# remote_v0_9.net
KiCad netlist of a schematic drawn in EAGLE
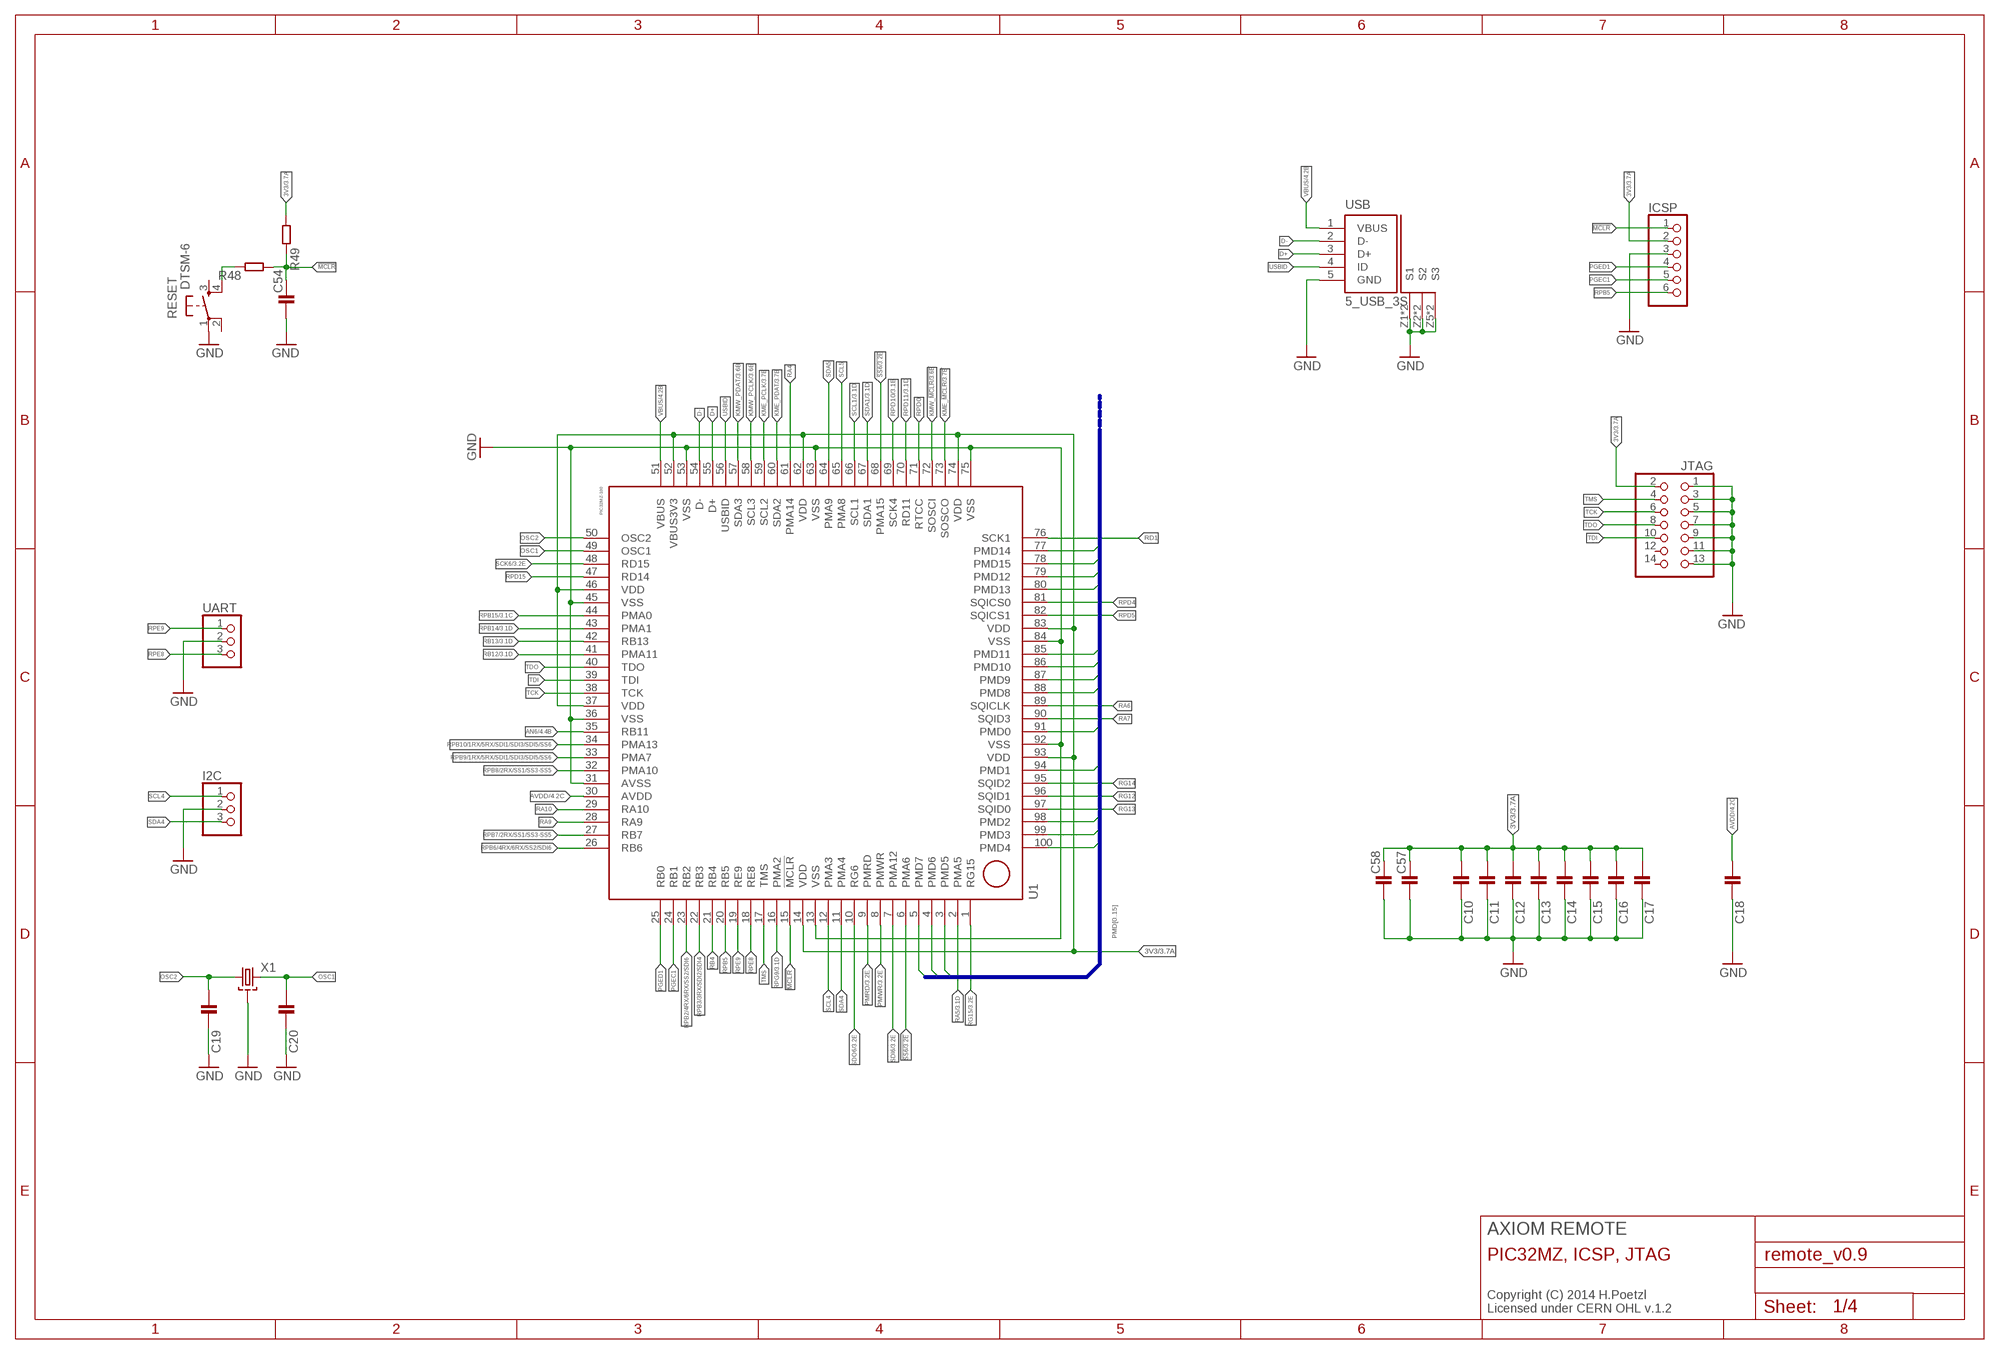
[diagram p0: schematic, sheet 1]
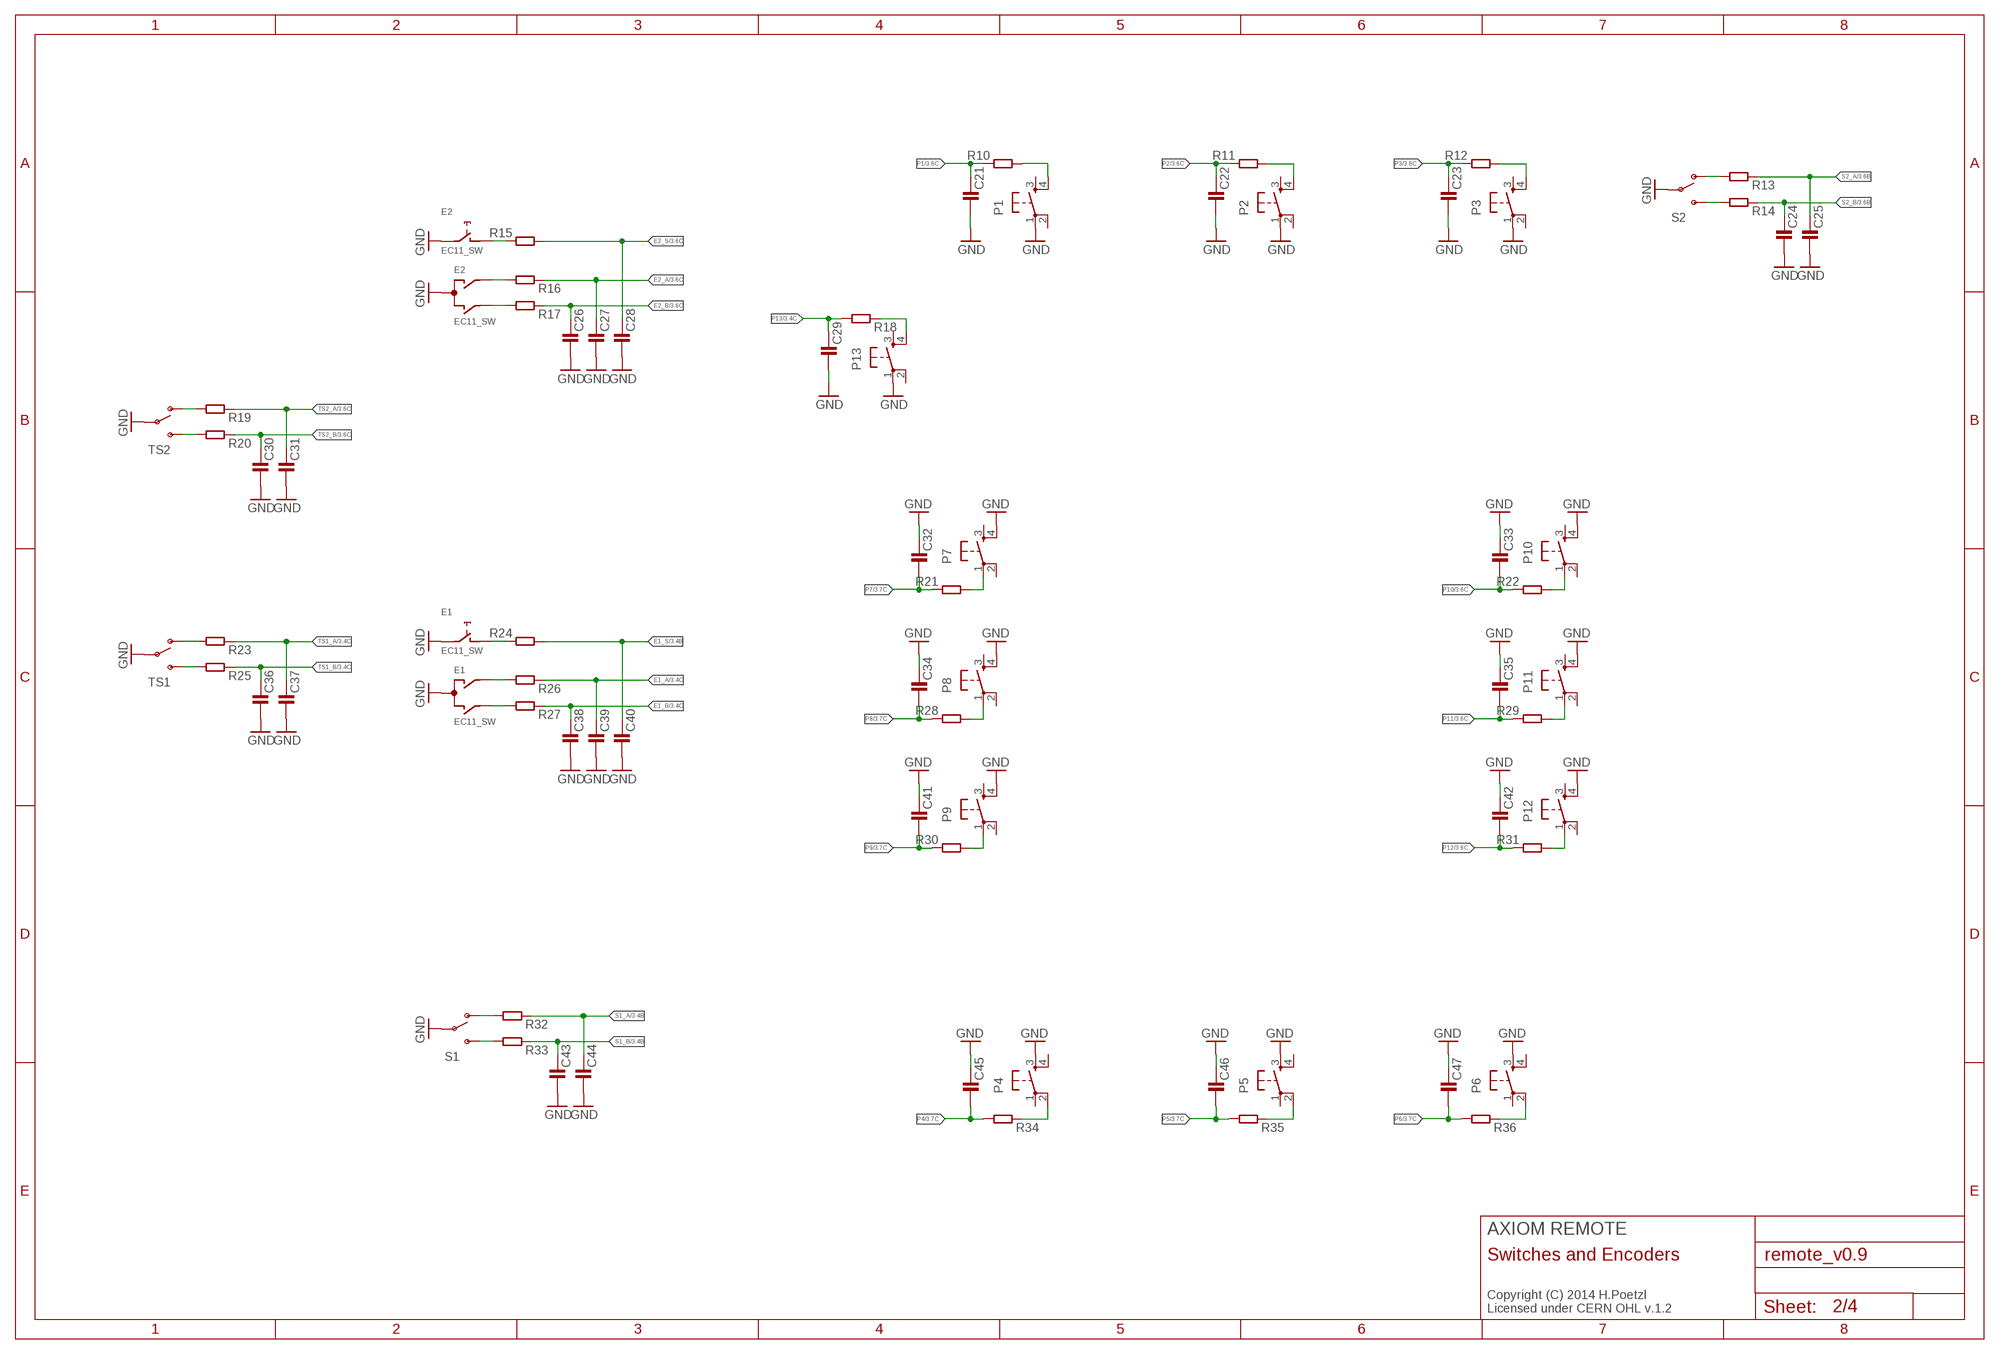
[diagram p1: schematic, sheet 2]
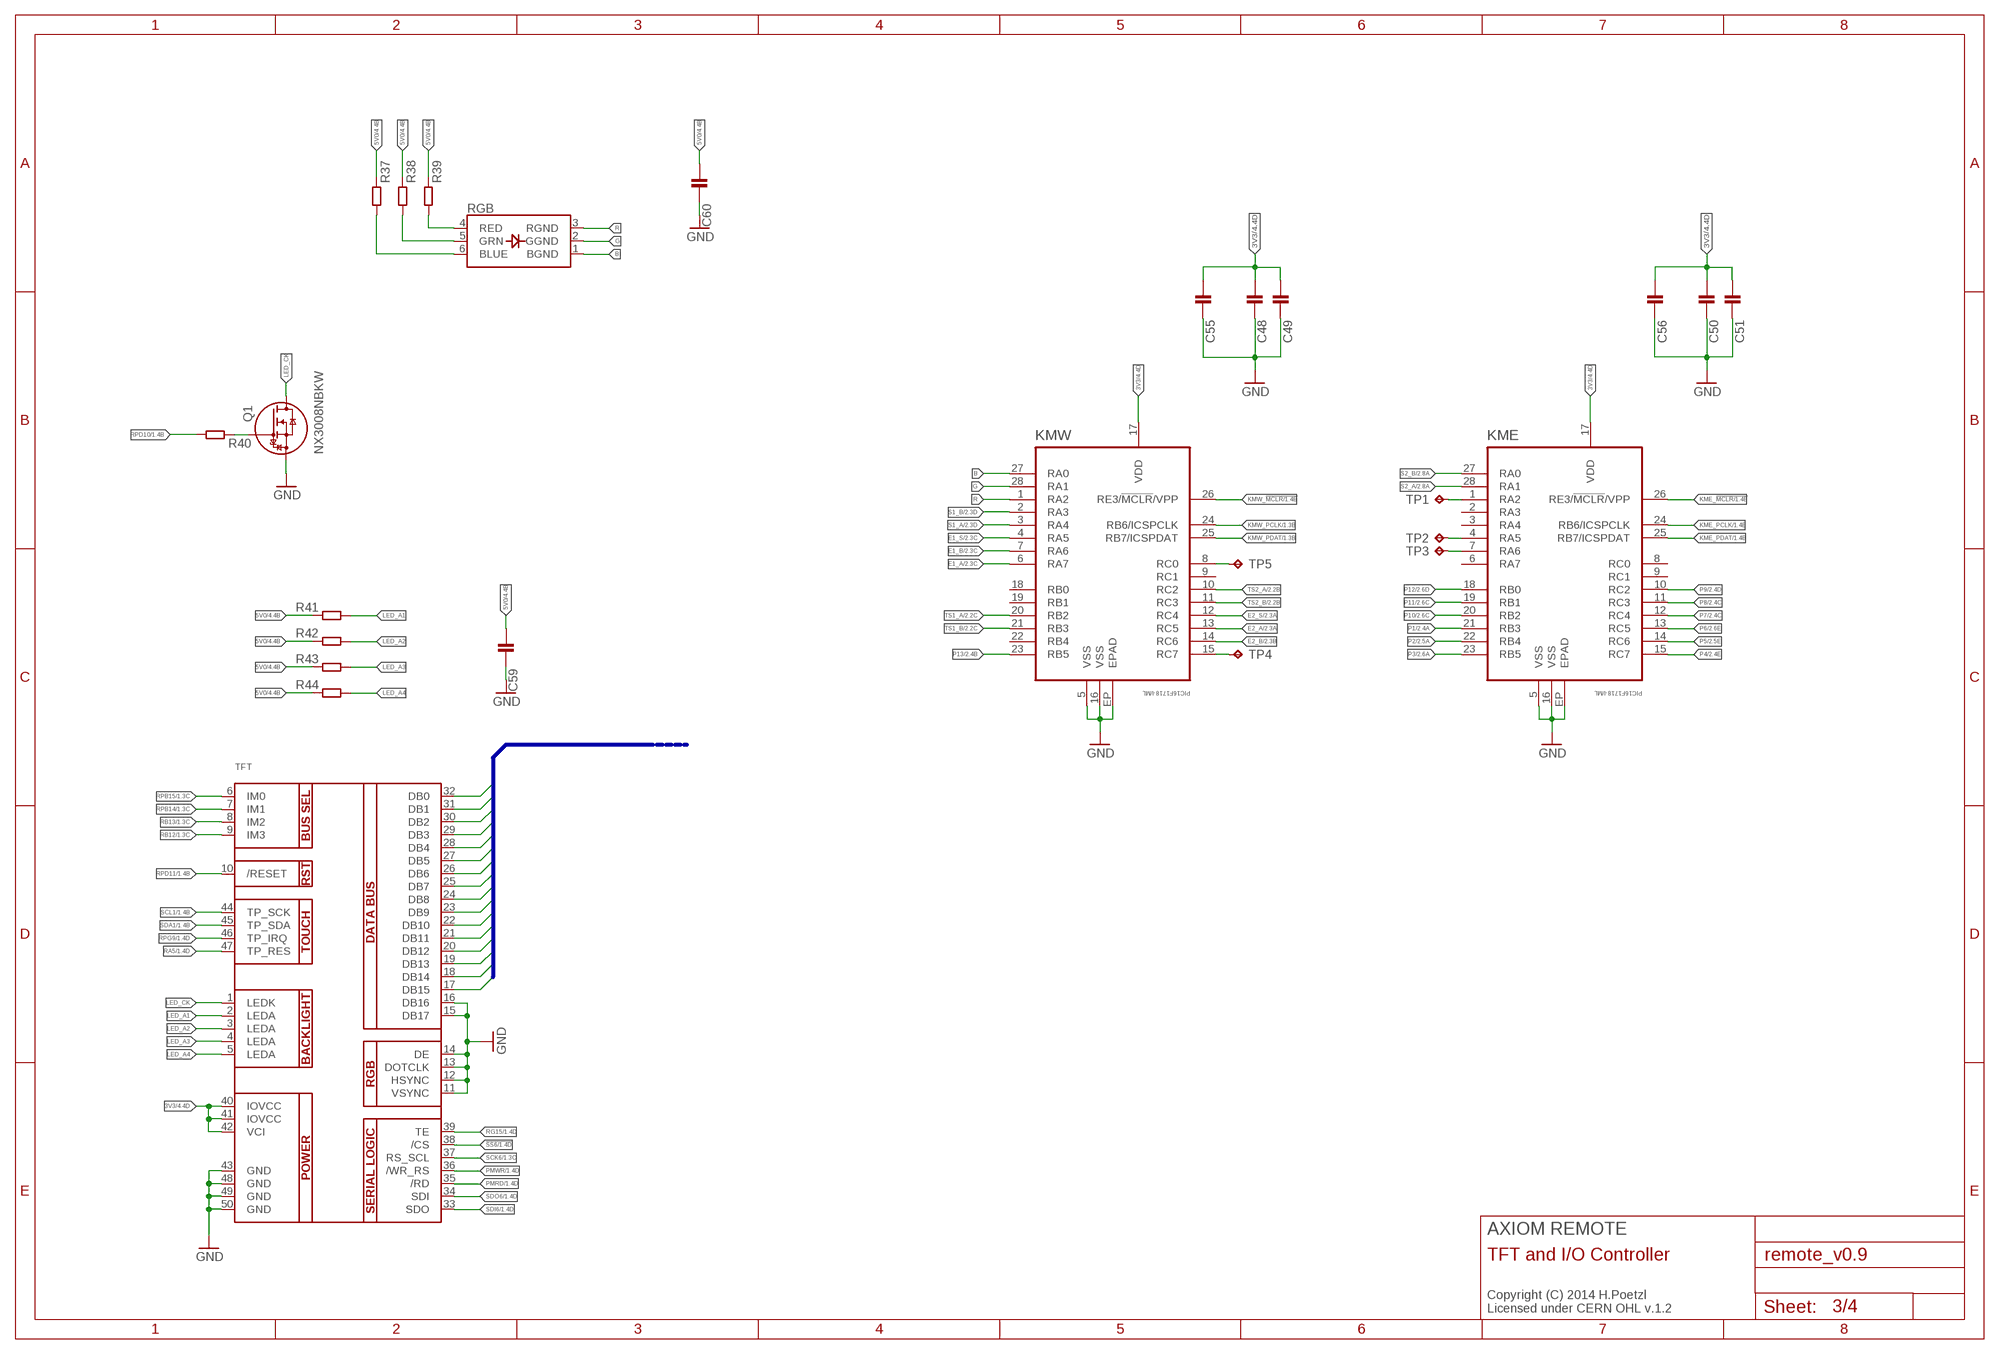
[diagram p2: schematic, sheet 3]
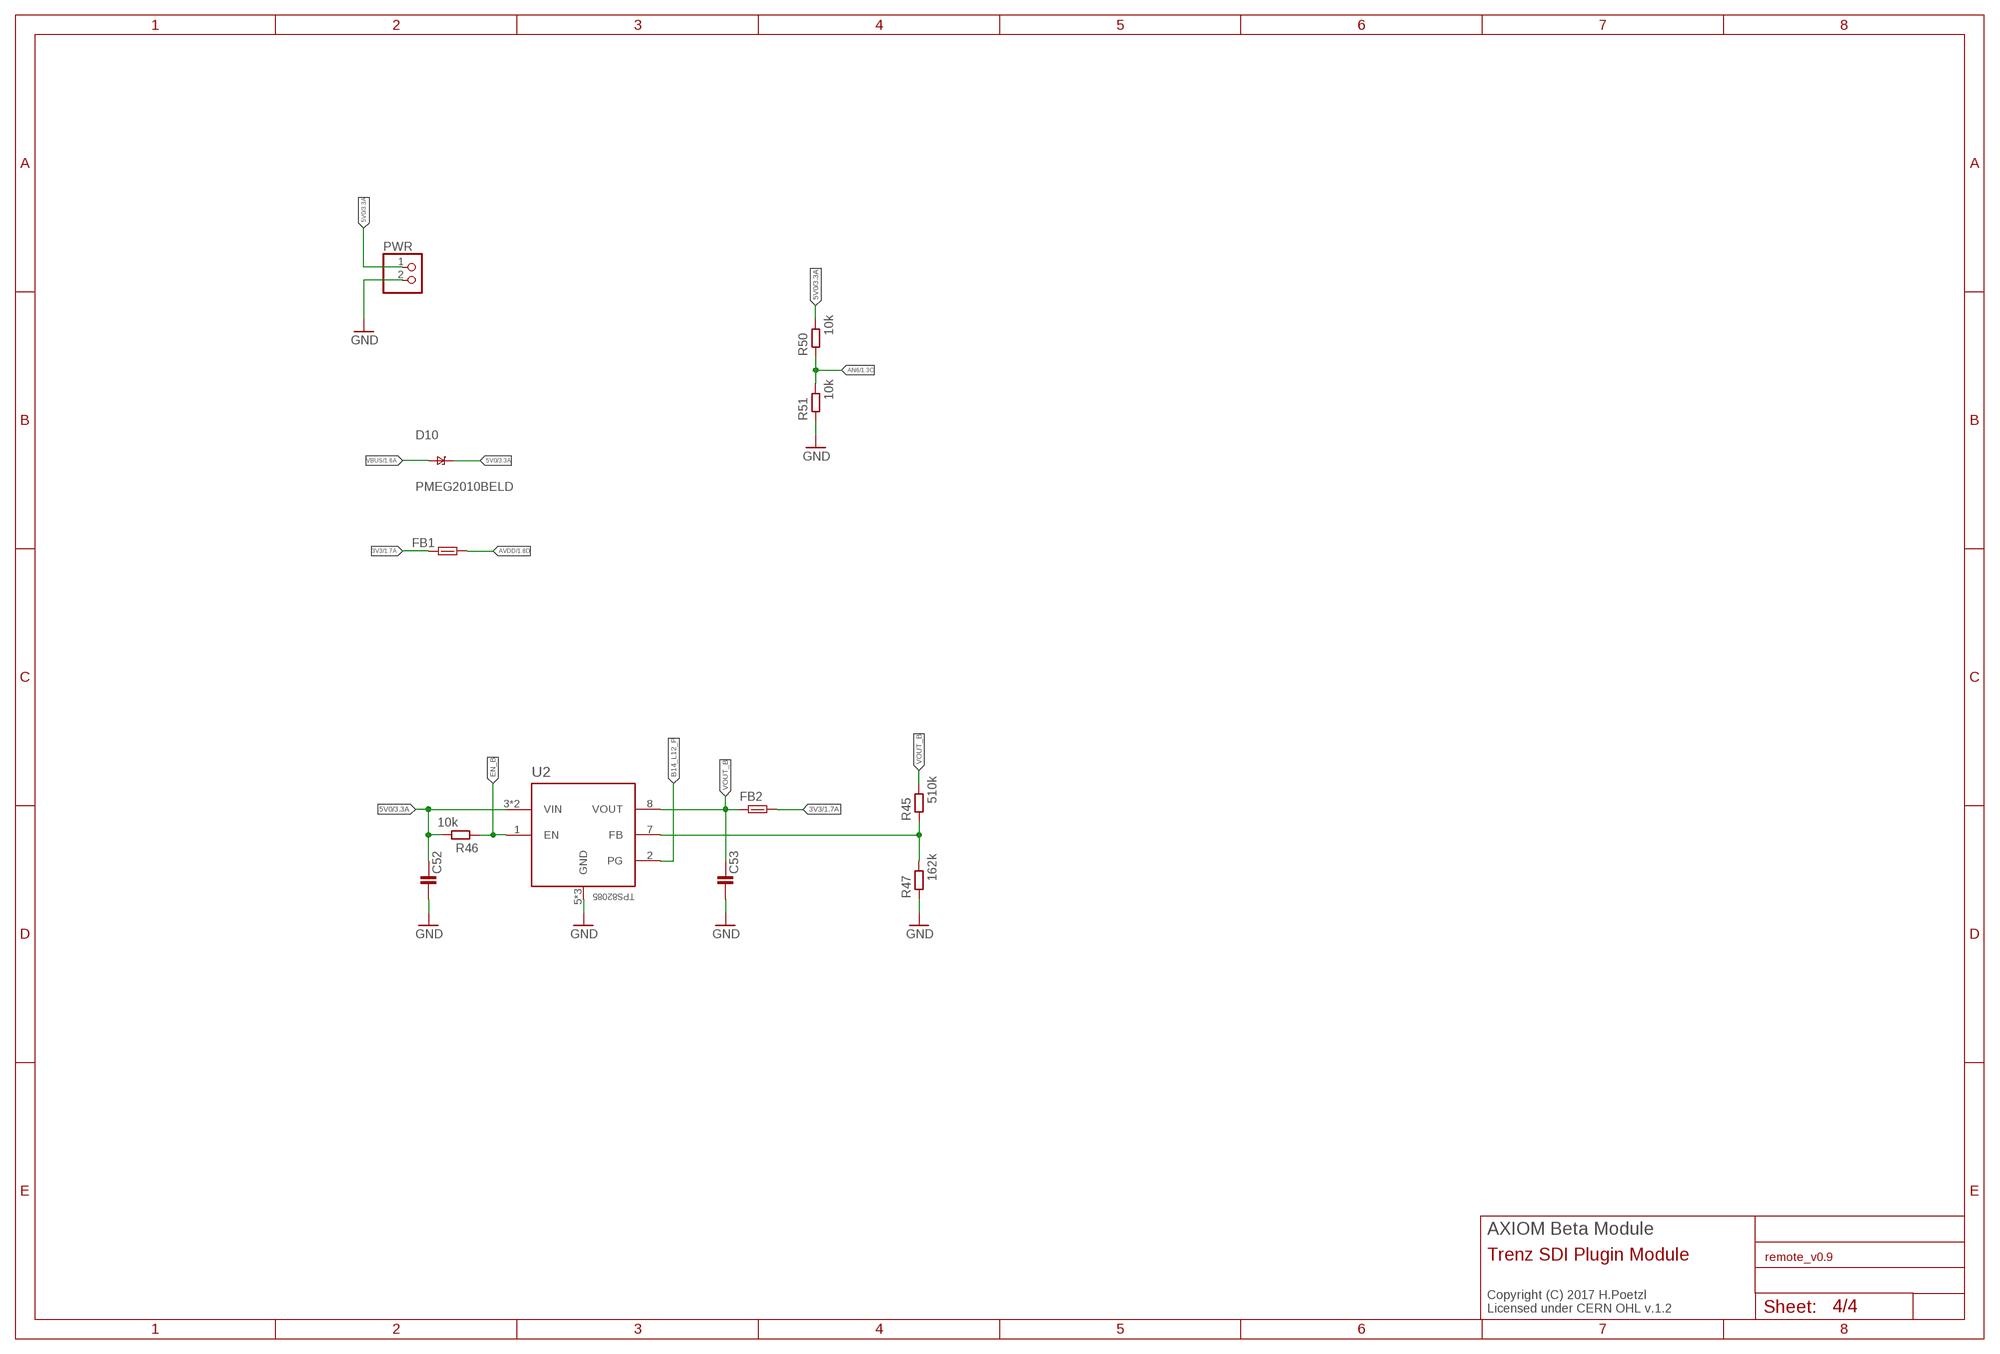
[diagram p3: schematic, sheet 4]

(export (version "E")
  (design (tool "Eeschema 10.0.6"))
  (components
    (comp (ref "C48")
      (value "100n")
      (footprint "eagle-import:0402-C")
      (libsource (lib "eagle-import") (part "C0402-C"))
    )
    (comp (ref "C49")
      (value "100n")
      (footprint "eagle-import:0402-C")
      (libsource (lib "eagle-import") (part "C0402-C"))
    )
    (comp (ref "C50")
      (value "100n")
      (footprint "eagle-import:0402-C")
      (libsource (lib "eagle-import") (part "C0402-C"))
    )
    (comp (ref "C51")
      (value "100n")
      (footprint "eagle-import:0402-C")
      (libsource (lib "eagle-import") (part "C0402-C"))
    )
    (comp (ref "C55")
      (value "100n")
      (footprint "eagle-import:0805-C")
      (libsource (lib "eagle-import") (part "C0805-C"))
    )
    (comp (ref "C56")
      (value "100n")
      (footprint "eagle-import:0805-C")
      (libsource (lib "eagle-import") (part "C0805-C"))
    )
    (comp (ref "C59")
      (value "100n")
      (footprint "eagle-import:0805-C")
      (libsource (lib "eagle-import") (part "C0805-C"))
    )
    (comp (ref "C60")
      (value "100n")
      (footprint "eagle-import:0805-C")
      (libsource (lib "eagle-import") (part "C0805-C"))
    )
    (comp (ref "KME")
      (value "PIC16F1718-I/ML")
      (footprint "eagle-import:QFN65P600X600X100-29N")
      (libsource (lib "eagle-import") (part "PIC16F1718-I/ML"))
    )
    (comp (ref "KMW")
      (value "PIC16F1718-I/ML")
      (footprint "eagle-import:QFN65P600X600X100-29N")
      (libsource (lib "eagle-import") (part "PIC16F1718-I/ML"))
    )
    (comp (ref "Q1")
      (value "NX3008NBKW")
      (footprint "eagle-import:SOT323")
      (libsource (lib "eagle-import") (part "NX3008NBKW"))
    )
    (comp (ref "R37")
      (value "R0603-C")
      (footprint "eagle-import:0603-C")
      (libsource (lib "eagle-import") (part "R0603-C"))
    )
    (comp (ref "R38")
      (value "R0603-C")
      (footprint "eagle-import:0603-C")
      (libsource (lib "eagle-import") (part "R0603-C"))
    )
    (comp (ref "R39")
      (value "R0603-C")
      (footprint "eagle-import:0603-C")
      (libsource (lib "eagle-import") (part "R0603-C"))
    )
    (comp (ref "R40")
      (value "R0402-C")
      (footprint "eagle-import:0402-C")
      (libsource (lib "eagle-import") (part "R0402-C"))
    )
    (comp (ref "R41")
      (value "R0805-C")
      (footprint "eagle-import:0805-C")
      (libsource (lib "eagle-import") (part "R0805-C"))
    )
    (comp (ref "R42")
      (value "R0805-C")
      (footprint "eagle-import:0805-C")
      (libsource (lib "eagle-import") (part "R0805-C"))
    )
    (comp (ref "R43")
      (value "R0805-C")
      (footprint "eagle-import:0805-C")
      (libsource (lib "eagle-import") (part "R0805-C"))
    )
    (comp (ref "R44")
      (value "R0805-C")
      (footprint "eagle-import:0805-C")
      (libsource (lib "eagle-import") (part "R0805-C"))
    )
    (comp (ref "RGB")
      (value "LED_RGB_PLCC6CREE-CLV6A")
      (footprint "eagle-import:RGBLED_PLCC6")
      (libsource (lib "eagle-import") (part "LED_RGB_PLCC6CREE-CLV6A"))
    )
    (comp (ref "TFT")
      (value "DISP_LCD_CTP28_SAMPLE")
      (footprint "eagle-import:TFT_2.83IN_240X320_50PIN")
      (libsource (lib "eagle-import") (part "DISP_LCD_CTP28_SAMPLE"))
    )
    (comp (ref "TP1")
      (value "TPTP12R")
      (footprint "eagle-import:TP12R")
      (libsource (lib "eagle-import") (part "TPTP12R"))
    )
    (comp (ref "TP2")
      (value "TPTP12R")
      (footprint "eagle-import:TP12R")
      (libsource (lib "eagle-import") (part "TPTP12R"))
    )
    (comp (ref "TP3")
      (value "TPTP12R")
      (footprint "eagle-import:TP12R")
      (libsource (lib "eagle-import") (part "TPTP12R"))
    )
    (comp (ref "TP4")
      (value "TPTP12R")
      (footprint "eagle-import:TP12R")
      (libsource (lib "eagle-import") (part "TPTP12R"))
    )
    (comp (ref "TP5")
      (value "TPTP12R")
      (footprint "eagle-import:TP12R")
      (libsource (lib "eagle-import") (part "TPTP12R"))
    )
    (comp (ref "C52")
      (value "C0603-C")
      (footprint "eagle-import:0603-C")
      (libsource (lib "eagle-import") (part "C0603-C"))
    )
    (comp (ref "C53")
      (value "C0603-C")
      (footprint "eagle-import:0603-C")
      (libsource (lib "eagle-import") (part "C0603-C"))
    )
    (comp (ref "D10")
      (value "PMEG2010BELD")
      (footprint "eagle-import:DFN1006D-2")
      (libsource (lib "eagle-import") (part "PMEG2010BELD"))
    )
    (comp (ref "FB1")
      (value "FB0402-C")
      (footprint "eagle-import:0402-C")
      (libsource (lib "eagle-import") (part "FB0402-C"))
    )
    (comp (ref "FB2")
      (value "FB0603-C")
      (footprint "eagle-import:0603-C")
      (libsource (lib "eagle-import") (part "FB0603-C"))
    )
    (comp (ref "PWR")
      (value "PINHD-1X02_2.54-90°")
      (footprint "eagle-import:1X02_90")
      (libsource (lib "eagle-import") (part "PINHD-1X02_2.54-90°"))
    )
    (comp (ref "R45")
      (value "510k")
      (footprint "eagle-import:0201-C")
      (libsource (lib "eagle-import") (part "R0201-C"))
    )
    (comp (ref "R46")
      (value "10k")
      (footprint "eagle-import:0201-C")
      (libsource (lib "eagle-import") (part "R0201-C"))
    )
    (comp (ref "R47")
      (value "162k")
      (footprint "eagle-import:0201-C")
      (libsource (lib "eagle-import") (part "R0201-C"))
    )
    (comp (ref "R50")
      (value "10k")
      (footprint "eagle-import:0402-C")
      (libsource (lib "eagle-import") (part "R0402-C"))
    )
    (comp (ref "R51")
      (value "10k")
      (footprint "eagle-import:0402-C")
      (libsource (lib "eagle-import") (part "R0402-C"))
    )
    (comp (ref "U2")
      (value "TPS82085")
      (footprint "eagle-import:MICROSIP")
      (libsource (lib "eagle-import") (part "TPS82085"))
    )
    (comp (ref "C21")
      (value "C0402-C")
      (footprint "eagle-import:0402-C")
      (libsource (lib "eagle-import") (part "C0402-C"))
    )
    (comp (ref "C22")
      (value "C0402-C")
      (footprint "eagle-import:0402-C")
      (libsource (lib "eagle-import") (part "C0402-C"))
    )
    (comp (ref "C23")
      (value "C0402-C")
      (footprint "eagle-import:0402-C")
      (libsource (lib "eagle-import") (part "C0402-C"))
    )
    (comp (ref "C24")
      (value "C0402-C")
      (footprint "eagle-import:0402-C")
      (libsource (lib "eagle-import") (part "C0402-C"))
    )
    (comp (ref "C25")
      (value "C0402-C")
      (footprint "eagle-import:0402-C")
      (libsource (lib "eagle-import") (part "C0402-C"))
    )
    (comp (ref "C26")
      (value "C0402-C")
      (footprint "eagle-import:0402-C")
      (libsource (lib "eagle-import") (part "C0402-C"))
    )
    (comp (ref "C27")
      (value "C0402-C")
      (footprint "eagle-import:0402-C")
      (libsource (lib "eagle-import") (part "C0402-C"))
    )
    (comp (ref "C28")
      (value "C0402-C")
      (footprint "eagle-import:0402-C")
      (libsource (lib "eagle-import") (part "C0402-C"))
    )
    (comp (ref "C29")
      (value "C0402-C")
      (footprint "eagle-import:0402-C")
      (libsource (lib "eagle-import") (part "C0402-C"))
    )
    (comp (ref "C30")
      (value "C0402-C")
      (footprint "eagle-import:0402-C")
      (libsource (lib "eagle-import") (part "C0402-C"))
    )
    (comp (ref "C31")
      (value "C0402-C")
      (footprint "eagle-import:0402-C")
      (libsource (lib "eagle-import") (part "C0402-C"))
    )
    (comp (ref "C32")
      (value "C0402-C")
      (footprint "eagle-import:0402-C")
      (libsource (lib "eagle-import") (part "C0402-C"))
    )
    (comp (ref "C33")
      (value "C0402-C")
      (footprint "eagle-import:0402-C")
      (libsource (lib "eagle-import") (part "C0402-C"))
    )
    (comp (ref "C34")
      (value "C0402-C")
      (footprint "eagle-import:0402-C")
      (libsource (lib "eagle-import") (part "C0402-C"))
    )
    (comp (ref "C35")
      (value "C0402-C")
      (footprint "eagle-import:0402-C")
      (libsource (lib "eagle-import") (part "C0402-C"))
    )
    (comp (ref "C36")
      (value "C0402-C")
      (footprint "eagle-import:0402-C")
      (libsource (lib "eagle-import") (part "C0402-C"))
    )
    (comp (ref "C37")
      (value "C0402-C")
      (footprint "eagle-import:0402-C")
      (libsource (lib "eagle-import") (part "C0402-C"))
    )
    (comp (ref "C38")
      (value "C0402-C")
      (footprint "eagle-import:0402-C")
      (libsource (lib "eagle-import") (part "C0402-C"))
    )
    (comp (ref "C39")
      (value "C0402-C")
      (footprint "eagle-import:0402-C")
      (libsource (lib "eagle-import") (part "C0402-C"))
    )
    (comp (ref "C40")
      (value "C0402-C")
      (footprint "eagle-import:0402-C")
      (libsource (lib "eagle-import") (part "C0402-C"))
    )
    (comp (ref "C41")
      (value "C0402-C")
      (footprint "eagle-import:0402-C")
      (libsource (lib "eagle-import") (part "C0402-C"))
    )
    (comp (ref "C42")
      (value "C0402-C")
      (footprint "eagle-import:0402-C")
      (libsource (lib "eagle-import") (part "C0402-C"))
    )
    (comp (ref "C43")
      (value "C0402-C")
      (footprint "eagle-import:0402-C")
      (libsource (lib "eagle-import") (part "C0402-C"))
    )
    (comp (ref "C44")
      (value "C0402-C")
      (footprint "eagle-import:0402-C")
      (libsource (lib "eagle-import") (part "C0402-C"))
    )
    (comp (ref "C45")
      (value "C0402-C")
      (footprint "eagle-import:0402-C")
      (libsource (lib "eagle-import") (part "C0402-C"))
    )
    (comp (ref "C46")
      (value "C0402-C")
      (footprint "eagle-import:0402-C")
      (libsource (lib "eagle-import") (part "C0402-C"))
    )
    (comp (ref "C47")
      (value "C0402-C")
      (footprint "eagle-import:0402-C")
      (libsource (lib "eagle-import") (part "C0402-C"))
    )
    (comp (ref "E1")
      (value "EC11_SW")
      (footprint "eagle-import:EC11_SW")
      (libsource (lib "eagle-import") (part "EC11_SW"))
    )
    (comp (ref "E2")
      (value "EC11_SW")
      (footprint "eagle-import:EC11_SW")
      (libsource (lib "eagle-import") (part "EC11_SW"))
    )
    (comp (ref "P1")
      (value "DTSM-6THT")
      (footprint "eagle-import:6X6-THT")
      (libsource (lib "eagle-import") (part "DTSM-6THT"))
    )
    (comp (ref "P2")
      (value "DTSM-6THT")
      (footprint "eagle-import:6X6-THT")
      (libsource (lib "eagle-import") (part "DTSM-6THT"))
    )
    (comp (ref "P3")
      (value "DTSM-6THT")
      (footprint "eagle-import:6X6-THT")
      (libsource (lib "eagle-import") (part "DTSM-6THT"))
    )
    (comp (ref "P4")
      (value "DTSM-6THT")
      (footprint "eagle-import:6X6-THT")
      (libsource (lib "eagle-import") (part "DTSM-6THT"))
    )
    (comp (ref "P5")
      (value "DTSM-6THT")
      (footprint "eagle-import:6X6-THT")
      (libsource (lib "eagle-import") (part "DTSM-6THT"))
    )
    (comp (ref "P6")
      (value "DTSM-6THT")
      (footprint "eagle-import:6X6-THT")
      (libsource (lib "eagle-import") (part "DTSM-6THT"))
    )
    (comp (ref "P7")
      (value "DTSM-6THT")
      (footprint "eagle-import:6X6-THT")
      (libsource (lib "eagle-import") (part "DTSM-6THT"))
    )
    (comp (ref "P8")
      (value "DTSM-6THT")
      (footprint "eagle-import:6X6-THT")
      (libsource (lib "eagle-import") (part "DTSM-6THT"))
    )
    (comp (ref "P9")
      (value "DTSM-6THT")
      (footprint "eagle-import:6X6-THT")
      (libsource (lib "eagle-import") (part "DTSM-6THT"))
    )
    (comp (ref "P10")
      (value "DTSM-6THT")
      (footprint "eagle-import:6X6-THT")
      (libsource (lib "eagle-import") (part "DTSM-6THT"))
    )
    (comp (ref "P11")
      (value "DTSM-6THT")
      (footprint "eagle-import:6X6-THT")
      (libsource (lib "eagle-import") (part "DTSM-6THT"))
    )
    (comp (ref "P12")
      (value "DTSM-6THT")
      (footprint "eagle-import:6X6-THT")
      (libsource (lib "eagle-import") (part "DTSM-6THT"))
    )
    (comp (ref "P13")
      (value "DTSM-6THT")
      (footprint "eagle-import:6X6-THT")
      (libsource (lib "eagle-import") (part "DTSM-6THT"))
    )
    (comp (ref "R10")
      (value "R0402-C")
      (footprint "eagle-import:0402-C")
      (libsource (lib "eagle-import") (part "R0402-C"))
    )
    (comp (ref "R11")
      (value "R0402-C")
      (footprint "eagle-import:0402-C")
      (libsource (lib "eagle-import") (part "R0402-C"))
    )
    (comp (ref "R12")
      (value "R0402-C")
      (footprint "eagle-import:0402-C")
      (libsource (lib "eagle-import") (part "R0402-C"))
    )
    (comp (ref "R13")
      (value "R0402-C")
      (footprint "eagle-import:0402-C")
      (libsource (lib "eagle-import") (part "R0402-C"))
    )
    (comp (ref "R14")
      (value "R0402-C")
      (footprint "eagle-import:0402-C")
      (libsource (lib "eagle-import") (part "R0402-C"))
    )
    (comp (ref "R15")
      (value "R0402-C")
      (footprint "eagle-import:0402-C")
      (libsource (lib "eagle-import") (part "R0402-C"))
    )
    (comp (ref "R16")
      (value "R0402-C")
      (footprint "eagle-import:0402-C")
      (libsource (lib "eagle-import") (part "R0402-C"))
    )
    (comp (ref "R17")
      (value "R0402-C")
      (footprint "eagle-import:0402-C")
      (libsource (lib "eagle-import") (part "R0402-C"))
    )
    (comp (ref "R18")
      (value "R0402-C")
      (footprint "eagle-import:0402-C")
      (libsource (lib "eagle-import") (part "R0402-C"))
    )
    (comp (ref "R19")
      (value "R0402-C")
      (footprint "eagle-import:0402-C")
      (libsource (lib "eagle-import") (part "R0402-C"))
    )
    (comp (ref "R20")
      (value "R0402-C")
      (footprint "eagle-import:0402-C")
      (libsource (lib "eagle-import") (part "R0402-C"))
    )
    (comp (ref "R21")
      (value "R0402-C")
      (footprint "eagle-import:0402-C")
      (libsource (lib "eagle-import") (part "R0402-C"))
    )
    (comp (ref "R22")
      (value "R0402-C")
      (footprint "eagle-import:0402-C")
      (libsource (lib "eagle-import") (part "R0402-C"))
    )
    (comp (ref "R23")
      (value "R0402-C")
      (footprint "eagle-import:0402-C")
      (libsource (lib "eagle-import") (part "R0402-C"))
    )
    (comp (ref "R24")
      (value "R0402-C")
      (footprint "eagle-import:0402-C")
      (libsource (lib "eagle-import") (part "R0402-C"))
    )
    (comp (ref "R25")
      (value "R0402-C")
      (footprint "eagle-import:0402-C")
      (libsource (lib "eagle-import") (part "R0402-C"))
    )
    (comp (ref "R26")
      (value "R0402-C")
      (footprint "eagle-import:0402-C")
      (libsource (lib "eagle-import") (part "R0402-C"))
    )
    (comp (ref "R27")
      (value "R0402-C")
      (footprint "eagle-import:0402-C")
      (libsource (lib "eagle-import") (part "R0402-C"))
    )
    (comp (ref "R28")
      (value "R0402-C")
      (footprint "eagle-import:0402-C")
      (libsource (lib "eagle-import") (part "R0402-C"))
    )
    (comp (ref "R29")
      (value "R0402-C")
      (footprint "eagle-import:0402-C")
      (libsource (lib "eagle-import") (part "R0402-C"))
    )
    (comp (ref "R30")
      (value "R0402-C")
      (footprint "eagle-import:0402-C")
      (libsource (lib "eagle-import") (part "R0402-C"))
    )
    (comp (ref "R31")
      (value "R0402-C")
      (footprint "eagle-import:0402-C")
      (libsource (lib "eagle-import") (part "R0402-C"))
    )
    (comp (ref "R32")
      (value "R0402-C")
      (footprint "eagle-import:0402-C")
      (libsource (lib "eagle-import") (part "R0402-C"))
    )
    (comp (ref "R33")
      (value "R0402-C")
      (footprint "eagle-import:0402-C")
      (libsource (lib "eagle-import") (part "R0402-C"))
    )
    (comp (ref "R34")
      (value "R0402-C")
      (footprint "eagle-import:0402-C")
      (libsource (lib "eagle-import") (part "R0402-C"))
    )
    (comp (ref "R35")
      (value "R0402-C")
      (footprint "eagle-import:0402-C")
      (libsource (lib "eagle-import") (part "R0402-C"))
    )
    (comp (ref "R36")
      (value "R0402-C")
      (footprint "eagle-import:0402-C")
      (libsource (lib "eagle-import") (part "R0402-C"))
    )
    (comp (ref "S1")
      (value "SWITCH-SPDTTHT")
      (footprint "eagle-import:1101M2S3CBE2")
      (libsource (lib "eagle-import") (part "SWITCH-SPDTTHT"))
    )
    (comp (ref "S2")
      (value "SWITCH-SPDTTHT-RA")
      (footprint "eagle-import:1101M2S3ABE2")
      (libsource (lib "eagle-import") (part "SWITCH-SPDTTHT-RA"))
    )
    (comp (ref "TS1")
      (value "SWITCH-SPDTSTG-RA")
      (footprint "eagle-import:200SPXTXBXM6")
      (libsource (lib "eagle-import") (part "SWITCH-SPDTSTG-RA"))
    )
    (comp (ref "TS2")
      (value "SWITCH-SPDTSTG-RA")
      (footprint "eagle-import:200SPXTXBXM6")
      (libsource (lib "eagle-import") (part "SWITCH-SPDTSTG-RA"))
    )
    (comp (ref "C10")
      (value "100n")
      (footprint "eagle-import:0402-C")
      (libsource (lib "eagle-import") (part "C0402-C"))
    )
    (comp (ref "C11")
      (value "100n")
      (footprint "eagle-import:0402-C")
      (libsource (lib "eagle-import") (part "C0402-C"))
    )
    (comp (ref "C12")
      (value "100n")
      (footprint "eagle-import:0402-C")
      (libsource (lib "eagle-import") (part "C0402-C"))
    )
    (comp (ref "C13")
      (value "100n")
      (footprint "eagle-import:0402-C")
      (libsource (lib "eagle-import") (part "C0402-C"))
    )
    (comp (ref "C14")
      (value "100n")
      (footprint "eagle-import:0402-C")
      (libsource (lib "eagle-import") (part "C0402-C"))
    )
    (comp (ref "C15")
      (value "100n")
      (footprint "eagle-import:0402-C")
      (libsource (lib "eagle-import") (part "C0402-C"))
    )
    (comp (ref "C16")
      (value "100n")
      (footprint "eagle-import:0402-C")
      (libsource (lib "eagle-import") (part "C0402-C"))
    )
    (comp (ref "C17")
      (value "100n")
      (footprint "eagle-import:0402-C")
      (libsource (lib "eagle-import") (part "C0402-C"))
    )
    (comp (ref "C18")
      (value "100n")
      (footprint "eagle-import:0402-C")
      (libsource (lib "eagle-import") (part "C0402-C"))
    )
    (comp (ref "C19")
      (value "100n")
      (footprint "eagle-import:0402-C")
      (libsource (lib "eagle-import") (part "C0402-C"))
    )
    (comp (ref "C20")
      (value "100n")
      (footprint "eagle-import:0402-C")
      (libsource (lib "eagle-import") (part "C0402-C"))
    )
    (comp (ref "C54")
      (value "C0402-C")
      (footprint "eagle-import:0402-C")
      (libsource (lib "eagle-import") (part "C0402-C"))
    )
    (comp (ref "C57")
      (value "C0805-C")
      (footprint "eagle-import:0805-C")
      (libsource (lib "eagle-import") (part "C0805-C"))
    )
    (comp (ref "C58")
      (value "C0805-C")
      (footprint "eagle-import:0805-C")
      (libsource (lib "eagle-import") (part "C0805-C"))
    )
    (comp (ref "I2C")
      (value "PINHD-1X03_2.54-90°")
      (footprint "eagle-import:1X03_90")
      (libsource (lib "eagle-import") (part "PINHD-1X03_2.54-90°"))
    )
    (comp (ref "ICSP")
      (value "PINHD-1X6/90")
      (footprint "eagle-import:1X06_90")
      (libsource (lib "eagle-import") (part "PINHD-1X6/90"))
    )
    (comp (ref "JTAG")
      (value "PINHD-2X07_2.00")
      (footprint "eagle-import:2X07M")
      (libsource (lib "eagle-import") (part "PINHD-2X07_2.00"))
    )
    (comp (ref "R48")
      (value "R0402-C")
      (footprint "eagle-import:0402-C")
      (libsource (lib "eagle-import") (part "R0402-C"))
    )
    (comp (ref "R49")
      (value "R0402-C")
      (footprint "eagle-import:0402-C")
      (libsource (lib "eagle-import") (part "R0402-C"))
    )
    (comp (ref "RESET")
      (value "DTSM-6")
      (footprint "eagle-import:3X4MM")
      (libsource (lib "eagle-import") (part "DTSM-6"))
    )
    (comp (ref "U1")
      (value "PIC32MZ-100")
      (footprint "eagle-import:QFP40P1400X1400X120-100N")
      (libsource (lib "eagle-import") (part "PIC32MZ-100"))
    )
    (comp (ref "UART")
      (value "PINHD-1X03_2.54-90°")
      (footprint "eagle-import:1X03_90")
      (libsource (lib "eagle-import") (part "PINHD-1X03_2.54-90°"))
    )
    (comp (ref "USB")
      (value "5_USB_3S")
      (footprint "eagle-import:MICRO-AB-H-SMT")
      (libsource (lib "eagle-import") (part "5_USB_3S"))
    )
    (comp (ref "X1")
      (value "SMD-4P-2G-2.0X1.6")
      (footprint "eagle-import:2.0X1.6")
      (libsource (lib "eagle-import") (part "SMD-4P-2G-2.0X1.6"))
    )
  )
  (nets
    (net (code "2") (name "3V3") (class "Default")
      (node (ref "C10") (pin "1") (pinfunction "1_1") (pintype "passive"))
      (node (ref "C11") (pin "1") (pinfunction "1_1") (pintype "passive"))
      (node (ref "C12") (pin "1") (pinfunction "1_1") (pintype "passive"))
      (node (ref "C13") (pin "1") (pinfunction "1_1") (pintype "passive"))
      (node (ref "C14") (pin "1") (pinfunction "1_1") (pintype "passive"))
      (node (ref "C15") (pin "1") (pinfunction "1_1") (pintype "passive"))
      (node (ref "C16") (pin "1") (pinfunction "1_1") (pintype "passive"))
      (node (ref "C17") (pin "1") (pinfunction "1_1") (pintype "passive"))
      (node (ref "C48") (pin "1") (pinfunction "1_1") (pintype "passive"))
      (node (ref "C49") (pin "1") (pinfunction "1_1") (pintype "passive"))
      (node (ref "C50") (pin "1") (pinfunction "1_1") (pintype "passive"))
      (node (ref "C51") (pin "1") (pinfunction "1_1") (pintype "passive"))
      (node (ref "C55") (pin "1") (pinfunction "1_1") (pintype "passive"))
      (node (ref "C56") (pin "1") (pinfunction "1_1") (pintype "passive"))
      (node (ref "C57") (pin "1") (pinfunction "1_1") (pintype "passive"))
      (node (ref "C58") (pin "1") (pinfunction "1_1") (pintype "passive"))
      (node (ref "FB1") (pin "1") (pinfunction "1_1") (pintype "passive"))
      (node (ref "FB2") (pin "2") (pinfunction "2_2") (pintype "passive"))
      (node (ref "ICSP") (pin "2") (pinfunction "2_2") (pintype "passive"))
      (node (ref "JTAG") (pin "2") (pinfunction "2_2") (pintype "passive"))
      (node (ref "KME") (pin "17") (pinfunction "VDD_17") (pintype "power_in"))
      (node (ref "KMW") (pin "17") (pinfunction "VDD_17") (pintype "power_in"))
      (node (ref "R49") (pin "2") (pinfunction "2_2") (pintype "passive"))
      (node (ref "TFT") (pin "40") (pinfunction "IOVCC_40") (pintype "bidirectional"))
      (node (ref "TFT") (pin "41") (pinfunction "IOVCC_41") (pintype "bidirectional"))
      (node (ref "TFT") (pin "42") (pinfunction "VCI_42") (pintype "bidirectional"))
      (node (ref "U1") (pin "14") (pinfunction "VDD_14") (pintype "power_in"))
      (node (ref "U1") (pin "37") (pinfunction "VDD_37") (pintype "power_in"))
      (node (ref "U1") (pin "46") (pinfunction "VDD_46") (pintype "power_in"))
      (node (ref "U1") (pin "52") (pinfunction "VBUS3V3_52") (pintype "power_in"))
      (node (ref "U1") (pin "62") (pinfunction "VDD_62") (pintype "power_in"))
      (node (ref "U1") (pin "74") (pinfunction "VDD_74") (pintype "power_in"))
      (node (ref "U1") (pin "83") (pinfunction "VDD_83") (pintype "power_in"))
      (node (ref "U1") (pin "93") (pinfunction "VDD_93") (pintype "power_in"))
    )
    (net (code "3") (name "5V0") (class "Default")
      (node (ref "C52") (pin "1") (pinfunction "1_1") (pintype "passive"))
      (node (ref "C59") (pin "1") (pinfunction "1_1") (pintype "passive"))
      (node (ref "C60") (pin "1") (pinfunction "1_1") (pintype "passive"))
      (node (ref "D10") (pin "C") (pinfunction "K_C") (pintype "passive"))
      (node (ref "PWR") (pin "1") (pinfunction "1_1") (pintype "passive"))
      (node (ref "R37") (pin "1") (pinfunction "1_1") (pintype "passive"))
      (node (ref "R38") (pin "1") (pinfunction "1_1") (pintype "passive"))
      (node (ref "R39") (pin "1") (pinfunction "1_1") (pintype "passive"))
      (node (ref "R41") (pin "1") (pinfunction "1_1") (pintype "passive"))
      (node (ref "R42") (pin "1") (pinfunction "1_1") (pintype "passive"))
      (node (ref "R43") (pin "1") (pinfunction "1_1") (pintype "passive"))
      (node (ref "R44") (pin "1") (pinfunction "1_1") (pintype "passive"))
      (node (ref "R46") (pin "2") (pinfunction "2_2") (pintype "passive"))
      (node (ref "R50") (pin "2") (pinfunction "2_2") (pintype "passive"))
      (node (ref "U2") (pin "3") (pinfunction "VIN_3") (pintype "power_in"))
      (node (ref "U2") (pin "4") (pinfunction "VIN_4") (pintype "power_in"))
    )
    (net (code "4") (name "AN6") (class "Default")
      (node (ref "R50") (pin "1") (pinfunction "1_1") (pintype "passive"))
      (node (ref "R51") (pin "2") (pinfunction "2_2") (pintype "passive"))
      (node (ref "U1") (pin "35") (pinfunction "RB11_35") (pintype "bidirectional"))
    )
    (net (code "5") (name "AVDD") (class "Default")
      (node (ref "C18") (pin "1") (pinfunction "1_1") (pintype "passive"))
      (node (ref "FB1") (pin "2") (pinfunction "2_2") (pintype "passive"))
      (node (ref "U1") (pin "30") (pinfunction "AVDD_30") (pintype "power_in"))
    )
    (net (code "6") (name "B") (class "Default")
      (node (ref "KMW") (pin "27") (pinfunction "RA0_27") (pintype "bidirectional"))
      (node (ref "RGB") (pin "1") (pinfunction "BGND_1") (pintype "power_in"))
    )
    (net (code "7") (name "B14_L12_P") (class "Default")
      (node (ref "U2") (pin "2") (pinfunction "PG_2") (pintype "power_in"))
    )
    (net (code "8") (name "D+") (class "Default")
      (node (ref "U1") (pin "55") (pinfunction "D+_55") (pintype "bidirectional"))
      (node (ref "USB") (pin "3") (pinfunction "D+_3") (pintype "passive"))
    )
    (net (code "9") (name "D-") (class "Default")
      (node (ref "U1") (pin "54") (pinfunction "D-_54") (pintype "bidirectional"))
      (node (ref "USB") (pin "2") (pinfunction "D-_2") (pintype "passive"))
    )
    (net (code "10") (name "E1_A") (class "Default")
      (node (ref "C39") (pin "1") (pinfunction "1_1") (pintype "passive"))
      (node (ref "KMW") (pin "6") (pinfunction "RA7_6") (pintype "bidirectional"))
      (node (ref "R26") (pin "1") (pinfunction "1_1") (pintype "passive"))
    )
    (net (code "11") (name "E1_B") (class "Default")
      (node (ref "C38") (pin "1") (pinfunction "1_1") (pintype "passive"))
      (node (ref "KMW") (pin "7") (pinfunction "RA6_7") (pintype "bidirectional"))
      (node (ref "R27") (pin "1") (pinfunction "1_1") (pintype "passive"))
    )
    (net (code "12") (name "E1_S") (class "Default")
      (node (ref "C40") (pin "1") (pinfunction "1_1") (pintype "passive"))
      (node (ref "KMW") (pin "4") (pinfunction "RA5_4") (pintype "bidirectional"))
      (node (ref "R24") (pin "2") (pinfunction "2_2") (pintype "passive"))
    )
    (net (code "13") (name "E2_A") (class "Default")
      (node (ref "C27") (pin "1") (pinfunction "1_1") (pintype "passive"))
      (node (ref "KMW") (pin "13") (pinfunction "RC5_13") (pintype "bidirectional"))
      (node (ref "R16") (pin "1") (pinfunction "1_1") (pintype "passive"))
    )
    (net (code "14") (name "E2_B") (class "Default")
      (node (ref "C26") (pin "1") (pinfunction "1_1") (pintype "passive"))
      (node (ref "KMW") (pin "14") (pinfunction "RC6_14") (pintype "bidirectional"))
      (node (ref "R17") (pin "1") (pinfunction "1_1") (pintype "passive"))
    )
    (net (code "15") (name "E2_S") (class "Default")
      (node (ref "C28") (pin "1") (pinfunction "1_1") (pintype "passive"))
      (node (ref "KMW") (pin "12") (pinfunction "RC4_12") (pintype "bidirectional"))
      (node (ref "R15") (pin "2") (pinfunction "2_2") (pintype "passive"))
    )
    (net (code "16") (name "EN_B") (class "Default")
      (node (ref "R46") (pin "1") (pinfunction "1_1") (pintype "passive"))
      (node (ref "U2") (pin "1") (pinfunction "EN_1") (pintype "input"))
    )
    (net (code "17") (name "G") (class "Default")
      (node (ref "KMW") (pin "28") (pinfunction "RA1_28") (pintype "bidirectional"))
      (node (ref "RGB") (pin "2") (pinfunction "GGND_2") (pintype "power_in"))
    )
    (net (code "18") (name "GND") (class "Default")
      (node (ref "C10") (pin "2") (pinfunction "2_2") (pintype "passive"))
      (node (ref "C11") (pin "2") (pinfunction "2_2") (pintype "passive"))
      (node (ref "C12") (pin "2") (pinfunction "2_2") (pintype "passive"))
      (node (ref "C13") (pin "2") (pinfunction "2_2") (pintype "passive"))
      (node (ref "C14") (pin "2") (pinfunction "2_2") (pintype "passive"))
      (node (ref "C15") (pin "2") (pinfunction "2_2") (pintype "passive"))
      (node (ref "C16") (pin "2") (pinfunction "2_2") (pintype "passive"))
      (node (ref "C17") (pin "2") (pinfunction "2_2") (pintype "passive"))
      (node (ref "C18") (pin "2") (pinfunction "2_2") (pintype "passive"))
      (node (ref "C19") (pin "2") (pinfunction "2_2") (pintype "passive"))
      (node (ref "C20") (pin "2") (pinfunction "2_2") (pintype "passive"))
      (node (ref "C21") (pin "2") (pinfunction "2_2") (pintype "passive"))
      (node (ref "C22") (pin "2") (pinfunction "2_2") (pintype "passive"))
      (node (ref "C23") (pin "2") (pinfunction "2_2") (pintype "passive"))
      (node (ref "C24") (pin "2") (pinfunction "2_2") (pintype "passive"))
      (node (ref "C25") (pin "2") (pinfunction "2_2") (pintype "passive"))
      (node (ref "C26") (pin "2") (pinfunction "2_2") (pintype "passive"))
      (node (ref "C27") (pin "2") (pinfunction "2_2") (pintype "passive"))
      (node (ref "C28") (pin "2") (pinfunction "2_2") (pintype "passive"))
      (node (ref "C29") (pin "2") (pinfunction "2_2") (pintype "passive"))
      (node (ref "C30") (pin "2") (pinfunction "2_2") (pintype "passive"))
      (node (ref "C31") (pin "2") (pinfunction "2_2") (pintype "passive"))
      (node (ref "C32") (pin "1") (pinfunction "1_1") (pintype "passive"))
      (node (ref "C33") (pin "1") (pinfunction "1_1") (pintype "passive"))
      (node (ref "C34") (pin "1") (pinfunction "1_1") (pintype "passive"))
      (node (ref "C35") (pin "1") (pinfunction "1_1") (pintype "passive"))
      (node (ref "C36") (pin "2") (pinfunction "2_2") (pintype "passive"))
      (node (ref "C37") (pin "2") (pinfunction "2_2") (pintype "passive"))
      (node (ref "C38") (pin "2") (pinfunction "2_2") (pintype "passive"))
      (node (ref "C39") (pin "2") (pinfunction "2_2") (pintype "passive"))
      (node (ref "C40") (pin "2") (pinfunction "2_2") (pintype "passive"))
      (node (ref "C41") (pin "1") (pinfunction "1_1") (pintype "passive"))
      (node (ref "C42") (pin "1") (pinfunction "1_1") (pintype "passive"))
      (node (ref "C43") (pin "2") (pinfunction "2_2") (pintype "passive"))
      (node (ref "C44") (pin "2") (pinfunction "2_2") (pintype "passive"))
      (node (ref "C45") (pin "1") (pinfunction "1_1") (pintype "passive"))
      (node (ref "C46") (pin "1") (pinfunction "1_1") (pintype "passive"))
      (node (ref "C47") (pin "1") (pinfunction "1_1") (pintype "passive"))
      (node (ref "C48") (pin "2") (pinfunction "2_2") (pintype "passive"))
      (node (ref "C49") (pin "2") (pinfunction "2_2") (pintype "passive"))
      (node (ref "C50") (pin "2") (pinfunction "2_2") (pintype "passive"))
      (node (ref "C51") (pin "2") (pinfunction "2_2") (pintype "passive"))
      (node (ref "C52") (pin "2") (pinfunction "2_2") (pintype "passive"))
      (node (ref "C53") (pin "2") (pinfunction "2_2") (pintype "passive"))
      (node (ref "C54") (pin "2") (pinfunction "2_2") (pintype "passive"))
      (node (ref "C55") (pin "2") (pinfunction "2_2") (pintype "passive"))
      (node (ref "C56") (pin "2") (pinfunction "2_2") (pintype "passive"))
      (node (ref "C57") (pin "2") (pinfunction "2_2") (pintype "passive"))
      (node (ref "C58") (pin "2") (pinfunction "2_2") (pintype "passive"))
      (node (ref "C59") (pin "2") (pinfunction "2_2") (pintype "passive"))
      (node (ref "C60") (pin "2") (pinfunction "2_2") (pintype "passive"))
      (node (ref "E1") (pin "C") (pinfunction "C_C") (pintype "passive"))
      (node (ref "E1") (pin "E") (pinfunction "2_E") (pintype "passive"))
      (node (ref "E2") (pin "C") (pinfunction "C_C") (pintype "passive"))
      (node (ref "E2") (pin "E") (pinfunction "2_E") (pintype "passive"))
      (node (ref "I2C") (pin "2") (pinfunction "2_2") (pintype "passive"))
      (node (ref "ICSP") (pin "3") (pinfunction "3_3") (pintype "passive"))
      (node (ref "JTAG") (pin "1") (pinfunction "1_1") (pintype "passive"))
      (node (ref "JTAG") (pin "11") (pinfunction "11_11") (pintype "passive"))
      (node (ref "JTAG") (pin "13") (pinfunction "13_13") (pintype "passive"))
      (node (ref "JTAG") (pin "3") (pinfunction "3_3") (pintype "passive"))
      (node (ref "JTAG") (pin "5") (pinfunction "5_5") (pintype "passive"))
      (node (ref "JTAG") (pin "7") (pinfunction "7_7") (pintype "passive"))
      (node (ref "JTAG") (pin "9") (pinfunction "9_9") (pintype "passive"))
      (node (ref "KME") (pin "16") (pinfunction "VSS_16") (pintype "power_in"))
      (node (ref "KME") (pin "5") (pinfunction "VSS_5") (pintype "power_in"))
      (node (ref "KME") (pin "EP") (pinfunction "EPAD_EP") (pintype "passive"))
      (node (ref "KMW") (pin "16") (pinfunction "VSS_16") (pintype "power_in"))
      (node (ref "KMW") (pin "5") (pinfunction "VSS_5") (pintype "power_in"))
      (node (ref "KMW") (pin "EP") (pinfunction "EPAD_EP") (pintype "passive"))
      (node (ref "P1") (pin "1") (pinfunction "1_1") (pintype "passive"))
      (node (ref "P10") (pin "4") (pinfunction "4_4") (pintype "passive"))
      (node (ref "P11") (pin "4") (pinfunction "4_4") (pintype "passive"))
      (node (ref "P12") (pin "4") (pinfunction "4_4") (pintype "passive"))
      (node (ref "P13") (pin "1") (pinfunction "1_1") (pintype "passive"))
      (node (ref "P2") (pin "1") (pinfunction "1_1") (pintype "passive"))
      (node (ref "P3") (pin "1") (pinfunction "1_1") (pintype "passive"))
      (node (ref "P4") (pin "3") (pinfunction "3_3") (pintype "passive"))
      (node (ref "P5") (pin "3") (pinfunction "3_3") (pintype "passive"))
      (node (ref "P6") (pin "3") (pinfunction "3_3") (pintype "passive"))
      (node (ref "P7") (pin "4") (pinfunction "4_4") (pintype "passive"))
      (node (ref "P8") (pin "4") (pinfunction "4_4") (pintype "passive"))
      (node (ref "P9") (pin "4") (pinfunction "4_4") (pintype "passive"))
      (node (ref "PWR") (pin "2") (pinfunction "2_2") (pintype "passive"))
      (node (ref "Q1") (pin "2") (pinfunction "S_2") (pintype "passive"))
      (node (ref "R47") (pin "1") (pinfunction "1_1") (pintype "passive"))
      (node (ref "R51") (pin "1") (pinfunction "1_1") (pintype "passive"))
      (node (ref "RESET") (pin "1") (pinfunction "1_1") (pintype "passive"))
      (node (ref "S1") (pin "2") (pinfunction "P_2") (pintype "passive"))
      (node (ref "S2") (pin "2") (pinfunction "P_2") (pintype "passive"))
      (node (ref "TFT") (pin "11") (pinfunction "VSYNC_11") (pintype "bidirectional"))
      (node (ref "TFT") (pin "12") (pinfunction "HSYNC_12") (pintype "bidirectional"))
      (node (ref "TFT") (pin "13") (pinfunction "DOTCLK_13") (pintype "bidirectional"))
      (node (ref "TFT") (pin "14") (pinfunction "DE_14") (pintype "bidirectional"))
      (node (ref "TFT") (pin "15") (pinfunction "DB17_15") (pintype "bidirectional"))
      (node (ref "TFT") (pin "16") (pinfunction "DB16_16") (pintype "bidirectional"))
      (node (ref "TFT") (pin "43") (pinfunction "GND_43") (pintype "bidirectional"))
      (node (ref "TFT") (pin "48") (pinfunction "GND_48") (pintype "bidirectional"))
      (node (ref "TFT") (pin "49") (pinfunction "GND_49") (pintype "bidirectional"))
      (node (ref "TFT") (pin "50") (pinfunction "GND_50") (pintype "bidirectional"))
      (node (ref "TS1") (pin "2") (pinfunction "P_2") (pintype "passive"))
      (node (ref "TS2") (pin "2") (pinfunction "P_2") (pintype "passive"))
      (node (ref "U1") (pin "13") (pinfunction "VSS_13") (pintype "power_in"))
      (node (ref "U1") (pin "31") (pinfunction "AVSS_31") (pintype "power_in"))
      (node (ref "U1") (pin "36") (pinfunction "VSS_36") (pintype "power_in"))
      (node (ref "U1") (pin "45") (pinfunction "VSS_45") (pintype "power_in"))
      (node (ref "U1") (pin "53") (pinfunction "VSS_53") (pintype "power_in"))
      (node (ref "U1") (pin "63") (pinfunction "VSS_63") (pintype "power_in"))
      (node (ref "U1") (pin "75") (pinfunction "VSS_75") (pintype "power_in"))
      (node (ref "U1") (pin "84") (pinfunction "VSS_84") (pintype "power_in"))
      (node (ref "U1") (pin "92") (pinfunction "VSS_92") (pintype "power_in"))
      (node (ref "U2") (pin "5") (pinfunction "GND_5") (pintype "passive"))
      (node (ref "U2") (pin "6") (pinfunction "GND_6") (pintype "passive"))
      (node (ref "U2") (pin "EP") (pinfunction "GND_EP") (pintype "passive"))
      (node (ref "UART") (pin "2") (pinfunction "2_2") (pintype "passive"))
      (node (ref "USB") (pin "5") (pinfunction "GND_5") (pintype "passive"))
      (node (ref "USB") (pin "Z1") (pinfunction "S1_Z1") (pintype "passive"))
      (node (ref "USB") (pin "Z2") (pinfunction "S2_Z2") (pintype "passive"))
      (node (ref "USB") (pin "Z3") (pinfunction "S2_Z3") (pintype "passive"))
      (node (ref "USB") (pin "Z4") (pinfunction "S1_Z4") (pintype "passive"))
      (node (ref "USB") (pin "Z5") (pinfunction "S3_Z5") (pintype "passive"))
      (node (ref "USB") (pin "Z6") (pinfunction "S3_Z6") (pintype "passive"))
      (node (ref "X1") (pin "2") (pinfunction "GND_2") (pintype "power_in"))
      (node (ref "X1") (pin "4") (pinfunction "GND_4") (pintype "power_in"))
    )
    (net (code "19") (name "KME_PCLK") (class "Default")
      (node (ref "KME") (pin "24") (pinfunction "RB6/ICSPCLK_24") (pintype "bidirectional"))
      (node (ref "U1") (pin "59") (pinfunction "SCL2_59") (pintype "bidirectional"))
    )
    (net (code "20") (name "KME_PDAT") (class "Default")
      (node (ref "KME") (pin "25") (pinfunction "RB7/ICSPDAT_25") (pintype "bidirectional"))
      (node (ref "U1") (pin "60") (pinfunction "SDA2_60") (pintype "bidirectional"))
    )
    (net (code "21") (name "KME_~{MCLR}") (class "Default")
      (node (ref "KME") (pin "26") (pinfunction "RE3/~{MCLR}/VPP_26") (pintype "bidirectional"))
      (node (ref "U1") (pin "73") (pinfunction "SOSCO_73") (pintype "bidirectional"))
    )
    (net (code "22") (name "KMW_PCLK") (class "Default")
      (node (ref "KMW") (pin "24") (pinfunction "RB6/ICSPCLK_24") (pintype "bidirectional"))
      (node (ref "U1") (pin "58") (pinfunction "SCL3_58") (pintype "bidirectional"))
    )
    (net (code "23") (name "KMW_PDAT") (class "Default")
      (node (ref "KMW") (pin "25") (pinfunction "RB7/ICSPDAT_25") (pintype "bidirectional"))
      (node (ref "U1") (pin "57") (pinfunction "SDA3_57") (pintype "bidirectional"))
    )
    (net (code "24") (name "KMW_~{MCLR}") (class "Default")
      (node (ref "KMW") (pin "26") (pinfunction "RE3/~{MCLR}/VPP_26") (pintype "bidirectional"))
      (node (ref "U1") (pin "72") (pinfunction "SOSCI_72") (pintype "bidirectional"))
    )
    (net (code "25") (name "LED_A1") (class "Default")
      (node (ref "R41") (pin "2") (pinfunction "2_2") (pintype "passive"))
      (node (ref "TFT") (pin "2") (pinfunction "LEDA_2") (pintype "bidirectional"))
    )
    (net (code "26") (name "LED_A2") (class "Default")
      (node (ref "R42") (pin "2") (pinfunction "2_2") (pintype "passive"))
      (node (ref "TFT") (pin "3") (pinfunction "LEDA_3") (pintype "bidirectional"))
    )
    (net (code "27") (name "LED_A3") (class "Default")
      (node (ref "R43") (pin "2") (pinfunction "2_2") (pintype "passive"))
      (node (ref "TFT") (pin "4") (pinfunction "LEDA_4") (pintype "bidirectional"))
    )
    (net (code "28") (name "LED_A4") (class "Default")
      (node (ref "R44") (pin "2") (pinfunction "2_2") (pintype "passive"))
      (node (ref "TFT") (pin "5") (pinfunction "LEDA_5") (pintype "bidirectional"))
    )
    (net (code "29") (name "LED_CK") (class "Default")
      (node (ref "Q1") (pin "3") (pinfunction "D_3") (pintype "passive"))
      (node (ref "TFT") (pin "1") (pinfunction "LEDK_1") (pintype "bidirectional"))
    )
    (net (code "30") (name "Net-(E1-PadA)") (class "Default")
      (node (ref "E1") (pin "A") (pinfunction "A_A") (pintype "passive"))
      (node (ref "R26") (pin "2") (pinfunction "2_2") (pintype "passive"))
    )
    (net (code "31") (name "Net-(E1-PadB)") (class "Default")
      (node (ref "E1") (pin "B") (pinfunction "B_B") (pintype "passive"))
      (node (ref "R27") (pin "2") (pinfunction "2_2") (pintype "passive"))
    )
    (net (code "32") (name "Net-(E1D-1)") (class "Default")
      (node (ref "E1") (pin "D") (pinfunction "1_D") (pintype "passive"))
      (node (ref "R24") (pin "1") (pinfunction "1_1") (pintype "passive"))
    )
    (net (code "33") (name "Net-(E2-PadA)") (class "Default")
      (node (ref "E2") (pin "A") (pinfunction "A_A") (pintype "passive"))
      (node (ref "R16") (pin "2") (pinfunction "2_2") (pintype "passive"))
    )
    (net (code "34") (name "Net-(E2-PadB)") (class "Default")
      (node (ref "E2") (pin "B") (pinfunction "B_B") (pintype "passive"))
      (node (ref "R17") (pin "2") (pinfunction "2_2") (pintype "passive"))
    )
    (net (code "35") (name "Net-(E2D-1)") (class "Default")
      (node (ref "E2") (pin "D") (pinfunction "1_D") (pintype "passive"))
      (node (ref "R15") (pin "1") (pinfunction "1_1") (pintype "passive"))
    )
    (net (code "36") (name "Net-(KME-RA2)") (class "Default")
      (node (ref "KME") (pin "1") (pinfunction "RA2_1") (pintype "bidirectional"))
      (node (ref "TP1") (pin "TP") (pinfunction "TP_TP") (pintype "input"))
    )
    (net (code "37") (name "Net-(KME-RA5)") (class "Default")
      (node (ref "KME") (pin "4") (pinfunction "RA5_4") (pintype "bidirectional"))
      (node (ref "TP2") (pin "TP") (pinfunction "TP_TP") (pintype "input"))
    )
    (net (code "38") (name "Net-(KME-RA6)") (class "Default")
      (node (ref "KME") (pin "7") (pinfunction "RA6_7") (pintype "bidirectional"))
      (node (ref "TP3") (pin "TP") (pinfunction "TP_TP") (pintype "input"))
    )
    (net (code "39") (name "Net-(KMW-RC0)") (class "Default")
      (node (ref "KMW") (pin "8") (pinfunction "RC0_8") (pintype "bidirectional"))
      (node (ref "TP5") (pin "TP") (pinfunction "TP_TP") (pintype "input"))
    )
    (net (code "40") (name "Net-(KMW-RC7)") (class "Default")
      (node (ref "KMW") (pin "15") (pinfunction "RC7_15") (pintype "bidirectional"))
      (node (ref "TP4") (pin "TP") (pinfunction "TP_TP") (pintype "input"))
    )
    (net (code "41") (name "Net-(P1-Pad4)") (class "Default")
      (node (ref "P1") (pin "4") (pinfunction "4_4") (pintype "passive"))
      (node (ref "R10") (pin "2") (pinfunction "2_2") (pintype "passive"))
    )
    (net (code "42") (name "Net-(P2-Pad4)") (class "Default")
      (node (ref "P2") (pin "4") (pinfunction "4_4") (pintype "passive"))
      (node (ref "R11") (pin "2") (pinfunction "2_2") (pintype "passive"))
    )
    (net (code "43") (name "Net-(P3-Pad4)") (class "Default")
      (node (ref "P3") (pin "4") (pinfunction "4_4") (pintype "passive"))
      (node (ref "R12") (pin "2") (pinfunction "2_2") (pintype "passive"))
    )
    (net (code "44") (name "Net-(P4-Pad2)") (class "Default")
      (node (ref "P4") (pin "2") (pinfunction "2_2") (pintype "passive"))
      (node (ref "R34") (pin "1") (pinfunction "1_1") (pintype "passive"))
    )
    (net (code "45") (name "Net-(P5-Pad2)") (class "Default")
      (node (ref "P5") (pin "2") (pinfunction "2_2") (pintype "passive"))
      (node (ref "R35") (pin "1") (pinfunction "1_1") (pintype "passive"))
    )
    (net (code "46") (name "Net-(P6-Pad2)") (class "Default")
      (node (ref "P6") (pin "2") (pinfunction "2_2") (pintype "passive"))
      (node (ref "R36") (pin "1") (pinfunction "1_1") (pintype "passive"))
    )
    (net (code "47") (name "Net-(P7-Pad1)") (class "Default")
      (node (ref "P7") (pin "1") (pinfunction "1_1") (pintype "passive"))
      (node (ref "R21") (pin "2") (pinfunction "2_2") (pintype "passive"))
    )
    (net (code "48") (name "Net-(P8-Pad1)") (class "Default")
      (node (ref "P8") (pin "1") (pinfunction "1_1") (pintype "passive"))
      (node (ref "R28") (pin "2") (pinfunction "2_2") (pintype "passive"))
    )
    (net (code "49") (name "Net-(P9-Pad1)") (class "Default")
      (node (ref "P9") (pin "1") (pinfunction "1_1") (pintype "passive"))
      (node (ref "R30") (pin "2") (pinfunction "2_2") (pintype "passive"))
    )
    (net (code "50") (name "Net-(P10-Pad1)") (class "Default")
      (node (ref "P10") (pin "1") (pinfunction "1_1") (pintype "passive"))
      (node (ref "R22") (pin "2") (pinfunction "2_2") (pintype "passive"))
    )
    (net (code "51") (name "Net-(P11-Pad1)") (class "Default")
      (node (ref "P11") (pin "1") (pinfunction "1_1") (pintype "passive"))
      (node (ref "R29") (pin "2") (pinfunction "2_2") (pintype "passive"))
    )
    (net (code "52") (name "Net-(P12-Pad1)") (class "Default")
      (node (ref "P12") (pin "1") (pinfunction "1_1") (pintype "passive"))
      (node (ref "R31") (pin "2") (pinfunction "2_2") (pintype "passive"))
    )
    (net (code "53") (name "Net-(P13-Pad4)") (class "Default")
      (node (ref "P13") (pin "4") (pinfunction "4_4") (pintype "passive"))
      (node (ref "R18") (pin "1") (pinfunction "1_1") (pintype "passive"))
    )
    (net (code "54") (name "Net-(Q1-G)") (class "Default")
      (node (ref "Q1") (pin "1") (pinfunction "G_1") (pintype "passive"))
      (node (ref "R40") (pin "1") (pinfunction "1_1") (pintype "passive"))
    )
    (net (code "55") (name "Net-(R48-Pad1)") (class "Default")
      (node (ref "R48") (pin "1") (pinfunction "1_1") (pintype "passive"))
      (node (ref "RESET") (pin "4") (pinfunction "4_4") (pintype "passive"))
    )
    (net (code "56") (name "Net-(RGB-BLUE)") (class "Default")
      (node (ref "R37") (pin "2") (pinfunction "2_2") (pintype "passive"))
      (node (ref "RGB") (pin "6") (pinfunction "BLUE_6") (pintype "bidirectional"))
    )
    (net (code "57") (name "Net-(RGB-GRN)") (class "Default")
      (node (ref "R38") (pin "2") (pinfunction "2_2") (pintype "passive"))
      (node (ref "RGB") (pin "5") (pinfunction "GRN_5") (pintype "bidirectional"))
    )
    (net (code "58") (name "Net-(RGB-RED)") (class "Default")
      (node (ref "R39") (pin "2") (pinfunction "2_2") (pintype "passive"))
      (node (ref "RGB") (pin "4") (pinfunction "RED_4") (pintype "bidirectional"))
    )
    (net (code "59") (name "Net-(S1-O)") (class "Default")
      (node (ref "R32") (pin "2") (pinfunction "2_2") (pintype "passive"))
      (node (ref "S1") (pin "1") (pinfunction "O_1") (pintype "passive"))
    )
    (net (code "60") (name "Net-(S1-S)") (class "Default")
      (node (ref "R33") (pin "2") (pinfunction "2_2") (pintype "passive"))
      (node (ref "S1") (pin "3") (pinfunction "S_3") (pintype "passive"))
    )
    (net (code "61") (name "Net-(S2-O)") (class "Default")
      (node (ref "R13") (pin "2") (pinfunction "2_2") (pintype "passive"))
      (node (ref "S2") (pin "1") (pinfunction "O_1") (pintype "passive"))
    )
    (net (code "62") (name "Net-(S2-S)") (class "Default")
      (node (ref "R14") (pin "2") (pinfunction "2_2") (pintype "passive"))
      (node (ref "S2") (pin "3") (pinfunction "S_3") (pintype "passive"))
    )
    (net (code "63") (name "Net-(TS1-O)") (class "Default")
      (node (ref "R23") (pin "2") (pinfunction "2_2") (pintype "passive"))
      (node (ref "TS1") (pin "1") (pinfunction "O_1") (pintype "passive"))
    )
    (net (code "64") (name "Net-(TS1-S)") (class "Default")
      (node (ref "R25") (pin "2") (pinfunction "2_2") (pintype "passive"))
      (node (ref "TS1") (pin "3") (pinfunction "S_3") (pintype "passive"))
    )
    (net (code "65") (name "Net-(TS2-O)") (class "Default")
      (node (ref "R19") (pin "2") (pinfunction "2_2") (pintype "passive"))
      (node (ref "TS2") (pin "1") (pinfunction "O_1") (pintype "passive"))
    )
    (net (code "66") (name "Net-(TS2-S)") (class "Default")
      (node (ref "R20") (pin "2") (pinfunction "2_2") (pintype "passive"))
      (node (ref "TS2") (pin "3") (pinfunction "S_3") (pintype "passive"))
    )
    (net (code "67") (name "Net-(U2-FB)") (class "Default")
      (node (ref "R45") (pin "1") (pinfunction "1_1") (pintype "passive"))
      (node (ref "R47") (pin "2") (pinfunction "2_2") (pintype "passive"))
      (node (ref "U2") (pin "7") (pinfunction "FB_7") (pintype "output"))
    )
    (net (code "68") (name "OSC1") (class "Default")
      (node (ref "C20") (pin "1") (pinfunction "1_1") (pintype "passive"))
      (node (ref "U1") (pin "49") (pinfunction "OSC1_49") (pintype "bidirectional"))
      (node (ref "X1") (pin "3") (pinfunction "2_3") (pintype "passive"))
    )
    (net (code "69") (name "OSC2") (class "Default")
      (node (ref "C19") (pin "1") (pinfunction "1_1") (pintype "passive"))
      (node (ref "U1") (pin "50") (pinfunction "OSC2_50") (pintype "bidirectional"))
      (node (ref "X1") (pin "1") (pinfunction "1_1") (pintype "passive"))
    )
    (net (code "70") (name "P1") (class "Default")
      (node (ref "C21") (pin "1") (pinfunction "1_1") (pintype "passive"))
      (node (ref "KME") (pin "21") (pinfunction "RB3_21") (pintype "bidirectional"))
      (node (ref "R10") (pin "1") (pinfunction "1_1") (pintype "passive"))
    )
    (net (code "71") (name "P2") (class "Default")
      (node (ref "C22") (pin "1") (pinfunction "1_1") (pintype "passive"))
      (node (ref "KME") (pin "22") (pinfunction "RB4_22") (pintype "bidirectional"))
      (node (ref "R11") (pin "1") (pinfunction "1_1") (pintype "passive"))
    )
    (net (code "72") (name "P3") (class "Default")
      (node (ref "C23") (pin "1") (pinfunction "1_1") (pintype "passive"))
      (node (ref "KME") (pin "23") (pinfunction "RB5_23") (pintype "bidirectional"))
      (node (ref "R12") (pin "1") (pinfunction "1_1") (pintype "passive"))
    )
    (net (code "73") (name "P4") (class "Default")
      (node (ref "C45") (pin "2") (pinfunction "2_2") (pintype "passive"))
      (node (ref "KME") (pin "15") (pinfunction "RC7_15") (pintype "bidirectional"))
      (node (ref "R34") (pin "2") (pinfunction "2_2") (pintype "passive"))
    )
    (net (code "74") (name "P5") (class "Default")
      (node (ref "C46") (pin "2") (pinfunction "2_2") (pintype "passive"))
      (node (ref "KME") (pin "14") (pinfunction "RC6_14") (pintype "bidirectional"))
      (node (ref "R35") (pin "2") (pinfunction "2_2") (pintype "passive"))
    )
    (net (code "75") (name "P6") (class "Default")
      (node (ref "C47") (pin "2") (pinfunction "2_2") (pintype "passive"))
      (node (ref "KME") (pin "13") (pinfunction "RC5_13") (pintype "bidirectional"))
      (node (ref "R36") (pin "2") (pinfunction "2_2") (pintype "passive"))
    )
    (net (code "76") (name "P7") (class "Default")
      (node (ref "C32") (pin "2") (pinfunction "2_2") (pintype "passive"))
      (node (ref "KME") (pin "12") (pinfunction "RC4_12") (pintype "bidirectional"))
      (node (ref "R21") (pin "1") (pinfunction "1_1") (pintype "passive"))
    )
    (net (code "77") (name "P8") (class "Default")
      (node (ref "C34") (pin "2") (pinfunction "2_2") (pintype "passive"))
      (node (ref "KME") (pin "11") (pinfunction "RC3_11") (pintype "bidirectional"))
      (node (ref "R28") (pin "1") (pinfunction "1_1") (pintype "passive"))
    )
    (net (code "78") (name "P9") (class "Default")
      (node (ref "C41") (pin "2") (pinfunction "2_2") (pintype "passive"))
      (node (ref "KME") (pin "10") (pinfunction "RC2_10") (pintype "bidirectional"))
      (node (ref "R30") (pin "1") (pinfunction "1_1") (pintype "passive"))
    )
    (net (code "79") (name "P10") (class "Default")
      (node (ref "C33") (pin "2") (pinfunction "2_2") (pintype "passive"))
      (node (ref "KME") (pin "20") (pinfunction "RB2_20") (pintype "bidirectional"))
      (node (ref "R22") (pin "1") (pinfunction "1_1") (pintype "passive"))
    )
    (net (code "80") (name "P11") (class "Default")
      (node (ref "C35") (pin "2") (pinfunction "2_2") (pintype "passive"))
      (node (ref "KME") (pin "19") (pinfunction "RB1_19") (pintype "bidirectional"))
      (node (ref "R29") (pin "1") (pinfunction "1_1") (pintype "passive"))
    )
    (net (code "81") (name "P12") (class "Default")
      (node (ref "C42") (pin "2") (pinfunction "2_2") (pintype "passive"))
      (node (ref "KME") (pin "18") (pinfunction "RB0_18") (pintype "bidirectional"))
      (node (ref "R31") (pin "1") (pinfunction "1_1") (pintype "passive"))
    )
    (net (code "82") (name "P13") (class "Default")
      (node (ref "C29") (pin "1") (pinfunction "1_1") (pintype "passive"))
      (node (ref "KMW") (pin "23") (pinfunction "RB5_23") (pintype "bidirectional"))
      (node (ref "R18") (pin "2") (pinfunction "2_2") (pintype "passive"))
    )
    (net (code "83") (name "PGEC1") (class "Default")
      (node (ref "ICSP") (pin "5") (pinfunction "5_5") (pintype "passive"))
      (node (ref "U1") (pin "24") (pinfunction "RB1_24") (pintype "bidirectional"))
    )
    (net (code "84") (name "PGED1") (class "Default")
      (node (ref "ICSP") (pin "4") (pinfunction "4_4") (pintype "passive"))
      (node (ref "U1") (pin "25") (pinfunction "RB0_25") (pintype "bidirectional"))
    )
    (net (code "85") (name "PMD0") (class "Default")
      (node (ref "TFT") (pin "32") (pinfunction "DB0_32") (pintype "bidirectional"))
      (node (ref "U1") (pin "91") (pinfunction "PMD0_91") (pintype "bidirectional"))
    )
    (net (code "86") (name "PMD1") (class "Default")
      (node (ref "TFT") (pin "31") (pinfunction "DB1_31") (pintype "bidirectional"))
      (node (ref "U1") (pin "94") (pinfunction "PMD1_94") (pintype "bidirectional"))
    )
    (net (code "87") (name "PMD2") (class "Default")
      (node (ref "TFT") (pin "30") (pinfunction "DB2_30") (pintype "bidirectional"))
      (node (ref "U1") (pin "98") (pinfunction "PMD2_98") (pintype "bidirectional"))
    )
    (net (code "88") (name "PMD3") (class "Default")
      (node (ref "TFT") (pin "29") (pinfunction "DB3_29") (pintype "bidirectional"))
      (node (ref "U1") (pin "99") (pinfunction "PMD3_99") (pintype "bidirectional"))
    )
    (net (code "89") (name "PMD4") (class "Default")
      (node (ref "TFT") (pin "28") (pinfunction "DB4_28") (pintype "bidirectional"))
      (node (ref "U1") (pin "100") (pinfunction "PMD4_100") (pintype "bidirectional"))
    )
    (net (code "90") (name "PMD5") (class "Default")
      (node (ref "TFT") (pin "27") (pinfunction "DB5_27") (pintype "bidirectional"))
      (node (ref "U1") (pin "3") (pinfunction "PMD5_3") (pintype "bidirectional"))
    )
    (net (code "91") (name "PMD6") (class "Default")
      (node (ref "TFT") (pin "26") (pinfunction "DB6_26") (pintype "bidirectional"))
      (node (ref "U1") (pin "4") (pinfunction "PMD6_4") (pintype "bidirectional"))
    )
    (net (code "92") (name "PMD7") (class "Default")
      (node (ref "TFT") (pin "25") (pinfunction "DB7_25") (pintype "bidirectional"))
      (node (ref "U1") (pin "5") (pinfunction "PMD7_5") (pintype "bidirectional"))
    )
    (net (code "93") (name "PMD8") (class "Default")
      (node (ref "TFT") (pin "24") (pinfunction "DB8_24") (pintype "bidirectional"))
      (node (ref "U1") (pin "88") (pinfunction "PMD8_88") (pintype "bidirectional"))
    )
    (net (code "94") (name "PMD9") (class "Default")
      (node (ref "TFT") (pin "23") (pinfunction "DB9_23") (pintype "bidirectional"))
      (node (ref "U1") (pin "87") (pinfunction "PMD9_87") (pintype "bidirectional"))
    )
    (net (code "95") (name "PMD10") (class "Default")
      (node (ref "TFT") (pin "22") (pinfunction "DB10_22") (pintype "bidirectional"))
      (node (ref "U1") (pin "86") (pinfunction "PMD10_86") (pintype "bidirectional"))
    )
    (net (code "96") (name "PMD11") (class "Default")
      (node (ref "TFT") (pin "21") (pinfunction "DB11_21") (pintype "bidirectional"))
      (node (ref "U1") (pin "85") (pinfunction "PMD11_85") (pintype "bidirectional"))
    )
    (net (code "97") (name "PMD12") (class "Default")
      (node (ref "TFT") (pin "20") (pinfunction "DB12_20") (pintype "bidirectional"))
      (node (ref "U1") (pin "79") (pinfunction "PMD12_79") (pintype "bidirectional"))
    )
    (net (code "98") (name "PMD13") (class "Default")
      (node (ref "TFT") (pin "19") (pinfunction "DB13_19") (pintype "bidirectional"))
      (node (ref "U1") (pin "80") (pinfunction "PMD13_80") (pintype "bidirectional"))
    )
    (net (code "99") (name "PMD14") (class "Default")
      (node (ref "TFT") (pin "18") (pinfunction "DB14_18") (pintype "bidirectional"))
      (node (ref "U1") (pin "77") (pinfunction "PMD14_77") (pintype "bidirectional"))
    )
    (net (code "100") (name "PMD15") (class "Default")
      (node (ref "TFT") (pin "17") (pinfunction "DB15_17") (pintype "bidirectional"))
      (node (ref "U1") (pin "78") (pinfunction "PMD15_78") (pintype "bidirectional"))
    )
    (net (code "101") (name "PMRD") (class "Default")
      (node (ref "TFT") (pin "35") (pinfunction "/RD_35") (pintype "bidirectional"))
      (node (ref "U1") (pin "9") (pinfunction "PMRD_9") (pintype "bidirectional"))
    )
    (net (code "102") (name "PMWR") (class "Default")
      (node (ref "TFT") (pin "36") (pinfunction "/WR_RS_36") (pintype "bidirectional"))
      (node (ref "U1") (pin "8") (pinfunction "PMWR_8") (pintype "bidirectional"))
    )
    (net (code "103") (name "R") (class "Default")
      (node (ref "KMW") (pin "1") (pinfunction "RA2_1") (pintype "bidirectional"))
      (node (ref "RGB") (pin "3") (pinfunction "RGND_3") (pintype "power_in"))
    )
    (net (code "104") (name "RA4") (class "Default")
      (node (ref "U1") (pin "61") (pinfunction "PMA14_61") (pintype "bidirectional"))
    )
    (net (code "105") (name "RA5") (class "Default")
      (node (ref "TFT") (pin "47") (pinfunction "TP_RES_47") (pintype "bidirectional"))
      (node (ref "U1") (pin "2") (pinfunction "PMA5_2") (pintype "bidirectional"))
    )
    (net (code "106") (name "RA6") (class "Default")
      (node (ref "U1") (pin "89") (pinfunction "SQICLK_89") (pintype "bidirectional"))
    )
    (net (code "107") (name "RA7") (class "Default")
      (node (ref "U1") (pin "90") (pinfunction "SQID3_90") (pintype "bidirectional"))
    )
    (net (code "108") (name "RA9") (class "Default")
      (node (ref "U1") (pin "28") (pinfunction "RA9_28") (pintype "bidirectional"))
    )
    (net (code "109") (name "RA10") (class "Default")
      (node (ref "U1") (pin "29") (pinfunction "RA10_29") (pintype "bidirectional"))
    )
    (net (code "110") (name "RB4") (class "Default")
      (node (ref "U1") (pin "21") (pinfunction "RB4_21") (pintype "bidirectional"))
    )
    (net (code "111") (name "RB12") (class "Default")
      (node (ref "TFT") (pin "9") (pinfunction "IM3_9") (pintype "bidirectional"))
      (node (ref "U1") (pin "41") (pinfunction "PMA11_41") (pintype "bidirectional"))
    )
    (net (code "112") (name "RB13") (class "Default")
      (node (ref "TFT") (pin "8") (pinfunction "IM2_8") (pintype "bidirectional"))
      (node (ref "U1") (pin "42") (pinfunction "RB13_42") (pintype "bidirectional"))
    )
    (net (code "113") (name "RD1") (class "Default")
      (node (ref "U1") (pin "76") (pinfunction "SCK1_76") (pintype "bidirectional"))
    )
    (net (code "114") (name "RG12") (class "Default")
      (node (ref "U1") (pin "96") (pinfunction "SQID1_96") (pintype "bidirectional"))
    )
    (net (code "115") (name "RG13") (class "Default")
      (node (ref "U1") (pin "97") (pinfunction "SQID0_97") (pintype "bidirectional"))
    )
    (net (code "116") (name "RG14") (class "Default")
      (node (ref "U1") (pin "95") (pinfunction "SQID2_95") (pintype "bidirectional"))
    )
    (net (code "117") (name "RG15") (class "Default")
      (node (ref "TFT") (pin "39") (pinfunction "TE_39") (pintype "bidirectional"))
      (node (ref "U1") (pin "1") (pinfunction "RG15_1") (pintype "bidirectional"))
    )
    (net (code "118") (name "RPB2{slash}4RX{slash}6RX{slash}SS2{slash}SDI6") (class "Default")
      (node (ref "U1") (pin "23") (pinfunction "RB2_23") (pintype "bidirectional"))
    )
    (net (code "119") (name "RPB3{slash}3RX{slash}SDI2{slash}SDI4") (class "Default")
      (node (ref "U1") (pin "22") (pinfunction "RB3_22") (pintype "bidirectional"))
    )
    (net (code "120") (name "RPB5") (class "Default")
      (node (ref "ICSP") (pin "6") (pinfunction "6_6") (pintype "passive"))
      (node (ref "U1") (pin "20") (pinfunction "RB5_20") (pintype "bidirectional"))
    )
    (net (code "121") (name "RPB6{slash}4RX{slash}6RX{slash}SS2{slash}SDI6") (class "Default")
      (node (ref "U1") (pin "26") (pinfunction "RB6_26") (pintype "bidirectional"))
    )
    (net (code "122") (name "RPB7{slash}2RX{slash}SS1{slash}SS3-SS5") (class "Default")
      (node (ref "U1") (pin "27") (pinfunction "RB7_27") (pintype "bidirectional"))
    )
    (net (code "123") (name "RPB8{slash}2RX{slash}SS1{slash}SS3-SS5") (class "Default")
      (node (ref "U1") (pin "32") (pinfunction "PMA10_32") (pintype "bidirectional"))
    )
    (net (code "124") (name "RPB9{slash}1RX{slash}5RX{slash}SDI1{slash}SDI3{slash}SDI5{slash}SS6") (class "Default")
      (node (ref "U1") (pin "33") (pinfunction "PMA7_33") (pintype "bidirectional"))
    )
    (net (code "125") (name "RPB10{slash}1RX{slash}5RX{slash}SDI1{slash}SDI3{slash}SDI5{slash}SS6") (class "Default")
      (node (ref "U1") (pin "34") (pinfunction "PMA13_34") (pintype "bidirectional"))
    )
    (net (code "126") (name "RPB14") (class "Default")
      (node (ref "TFT") (pin "7") (pinfunction "IM1_7") (pintype "bidirectional"))
      (node (ref "U1") (pin "43") (pinfunction "PMA1_43") (pintype "bidirectional"))
    )
    (net (code "127") (name "RPB15") (class "Default")
      (node (ref "TFT") (pin "6") (pinfunction "IM0_6") (pintype "bidirectional"))
      (node (ref "U1") (pin "44") (pinfunction "PMA0_44") (pintype "bidirectional"))
    )
    (net (code "128") (name "RPD0") (class "Default")
      (node (ref "U1") (pin "71") (pinfunction "RTCC_71") (pintype "bidirectional"))
    )
    (net (code "129") (name "RPD4") (class "Default")
      (node (ref "U1") (pin "81") (pinfunction "SQICS0_81") (pintype "bidirectional"))
    )
    (net (code "130") (name "RPD5") (class "Default")
      (node (ref "U1") (pin "82") (pinfunction "SQICS1_82") (pintype "bidirectional"))
    )
    (net (code "131") (name "RPD10") (class "Default")
      (node (ref "R40") (pin "2") (pinfunction "2_2") (pintype "passive"))
      (node (ref "U1") (pin "69") (pinfunction "SCK4_69") (pintype "bidirectional"))
    )
    (net (code "132") (name "RPD11") (class "Default")
      (node (ref "TFT") (pin "10") (pinfunction "/RESET_10") (pintype "bidirectional"))
      (node (ref "U1") (pin "70") (pinfunction "RD11_70") (pintype "bidirectional"))
    )
    (net (code "133") (name "RPD15") (class "Default")
      (node (ref "U1") (pin "47") (pinfunction "RD14_47") (pintype "bidirectional"))
    )
    (net (code "134") (name "RPE8") (class "Default")
      (node (ref "U1") (pin "18") (pinfunction "RE8_18") (pintype "bidirectional"))
      (node (ref "UART") (pin "3") (pinfunction "3_3") (pintype "passive"))
    )
    (net (code "135") (name "RPE9") (class "Default")
      (node (ref "U1") (pin "19") (pinfunction "RE9_19") (pintype "bidirectional"))
      (node (ref "UART") (pin "1") (pinfunction "1_1") (pintype "passive"))
    )
    (net (code "136") (name "RPG9") (class "Default")
      (node (ref "TFT") (pin "46") (pinfunction "TP_IRQ_46") (pintype "bidirectional"))
      (node (ref "U1") (pin "16") (pinfunction "PMA2_16") (pintype "bidirectional"))
    )
    (net (code "137") (name "S1_A") (class "Default")
      (node (ref "C44") (pin "1") (pinfunction "1_1") (pintype "passive"))
      (node (ref "KMW") (pin "3") (pinfunction "RA4_3") (pintype "bidirectional"))
      (node (ref "R32") (pin "1") (pinfunction "1_1") (pintype "passive"))
    )
    (net (code "138") (name "S1_B") (class "Default")
      (node (ref "C43") (pin "1") (pinfunction "1_1") (pintype "passive"))
      (node (ref "KMW") (pin "2") (pinfunction "RA3_2") (pintype "bidirectional"))
      (node (ref "R33") (pin "1") (pinfunction "1_1") (pintype "passive"))
    )
    (net (code "139") (name "S2_A") (class "Default")
      (node (ref "C25") (pin "1") (pinfunction "1_1") (pintype "passive"))
      (node (ref "KME") (pin "28") (pinfunction "RA1_28") (pintype "bidirectional"))
      (node (ref "R13") (pin "1") (pinfunction "1_1") (pintype "passive"))
    )
    (net (code "140") (name "S2_B") (class "Default")
      (node (ref "C24") (pin "1") (pinfunction "1_1") (pintype "passive"))
      (node (ref "KME") (pin "27") (pinfunction "RA0_27") (pintype "bidirectional"))
      (node (ref "R14") (pin "1") (pinfunction "1_1") (pintype "passive"))
    )
    (net (code "141") (name "SCK6") (class "Default")
      (node (ref "TFT") (pin "37") (pinfunction "RS_SCL_37") (pintype "bidirectional"))
      (node (ref "U1") (pin "48") (pinfunction "RD15_48") (pintype "bidirectional"))
    )
    (net (code "142") (name "SCL1") (class "Default")
      (node (ref "TFT") (pin "44") (pinfunction "TP_SCK_44") (pintype "bidirectional"))
      (node (ref "U1") (pin "66") (pinfunction "SCL1_66") (pintype "bidirectional"))
    )
    (net (code "143") (name "SCL4") (class "Default")
      (node (ref "I2C") (pin "1") (pinfunction "1_1") (pintype "passive"))
      (node (ref "U1") (pin "12") (pinfunction "PMA3_12") (pintype "bidirectional"))
    )
    (net (code "144") (name "SCL5") (class "Default")
      (node (ref "U1") (pin "65") (pinfunction "PMA8_65") (pintype "bidirectional"))
    )
    (net (code "145") (name "SDA1") (class "Default")
      (node (ref "TFT") (pin "45") (pinfunction "TP_SDA_45") (pintype "bidirectional"))
      (node (ref "U1") (pin "67") (pinfunction "SDA1_67") (pintype "bidirectional"))
    )
    (net (code "146") (name "SDA4") (class "Default")
      (node (ref "I2C") (pin "3") (pinfunction "3_3") (pintype "passive"))
      (node (ref "U1") (pin "11") (pinfunction "PMA4_11") (pintype "bidirectional"))
    )
    (net (code "147") (name "SDA5") (class "Default")
      (node (ref "U1") (pin "64") (pinfunction "PMA9_64") (pintype "bidirectional"))
    )
    (net (code "148") (name "SDI6") (class "Default")
      (node (ref "TFT") (pin "33") (pinfunction "SDO_33") (pintype "bidirectional"))
      (node (ref "U1") (pin "7") (pinfunction "PMA12_7") (pintype "bidirectional"))
    )
    (net (code "149") (name "SDO6") (class "Default")
      (node (ref "TFT") (pin "34") (pinfunction "SDI_34") (pintype "bidirectional"))
      (node (ref "U1") (pin "10") (pinfunction "RG6_10") (pintype "bidirectional"))
    )
    (net (code "150") (name "TCK") (class "Default")
      (node (ref "JTAG") (pin "6") (pinfunction "6_6") (pintype "passive"))
      (node (ref "U1") (pin "38") (pinfunction "TCK_38") (pintype "bidirectional"))
    )
    (net (code "151") (name "TDI") (class "Default")
      (node (ref "JTAG") (pin "10") (pinfunction "10_10") (pintype "passive"))
      (node (ref "U1") (pin "39") (pinfunction "TDI_39") (pintype "bidirectional"))
    )
    (net (code "152") (name "TDO") (class "Default")
      (node (ref "JTAG") (pin "8") (pinfunction "8_8") (pintype "passive"))
      (node (ref "U1") (pin "40") (pinfunction "TDO_40") (pintype "bidirectional"))
    )
    (net (code "153") (name "TMS") (class "Default")
      (node (ref "JTAG") (pin "4") (pinfunction "4_4") (pintype "passive"))
      (node (ref "U1") (pin "17") (pinfunction "TMS_17") (pintype "bidirectional"))
    )
    (net (code "154") (name "TS1_A") (class "Default")
      (node (ref "C37") (pin "1") (pinfunction "1_1") (pintype "passive"))
      (node (ref "KMW") (pin "20") (pinfunction "RB2_20") (pintype "bidirectional"))
      (node (ref "R23") (pin "1") (pinfunction "1_1") (pintype "passive"))
    )
    (net (code "155") (name "TS1_B") (class "Default")
      (node (ref "C36") (pin "1") (pinfunction "1_1") (pintype "passive"))
      (node (ref "KMW") (pin "21") (pinfunction "RB3_21") (pintype "bidirectional"))
      (node (ref "R25") (pin "1") (pinfunction "1_1") (pintype "passive"))
    )
    (net (code "156") (name "TS2_A") (class "Default")
      (node (ref "C31") (pin "1") (pinfunction "1_1") (pintype "passive"))
      (node (ref "KMW") (pin "10") (pinfunction "RC2_10") (pintype "bidirectional"))
      (node (ref "R19") (pin "1") (pinfunction "1_1") (pintype "passive"))
    )
    (net (code "157") (name "TS2_B") (class "Default")
      (node (ref "C30") (pin "1") (pinfunction "1_1") (pintype "passive"))
      (node (ref "KMW") (pin "11") (pinfunction "RC3_11") (pintype "bidirectional"))
      (node (ref "R20") (pin "1") (pinfunction "1_1") (pintype "passive"))
    )
    (net (code "158") (name "USBID") (class "Default")
      (node (ref "U1") (pin "56") (pinfunction "USBID_56") (pintype "bidirectional"))
      (node (ref "USB") (pin "4") (pinfunction "ID_4") (pintype "passive"))
    )
    (net (code "159") (name "VBUS") (class "Default")
      (node (ref "D10") (pin "A") (pinfunction "A_A") (pintype "passive"))
      (node (ref "U1") (pin "51") (pinfunction "VBUS_51") (pintype "power_in"))
      (node (ref "USB") (pin "1") (pinfunction "VBUS_1") (pintype "passive"))
    )
    (net (code "160") (name "VOUT_B") (class "Default")
      (node (ref "C53") (pin "1") (pinfunction "1_1") (pintype "passive"))
      (node (ref "FB2") (pin "1") (pinfunction "1_1") (pintype "passive"))
      (node (ref "R45") (pin "2") (pinfunction "2_2") (pintype "passive"))
      (node (ref "U2") (pin "8") (pinfunction "VOUT_8") (pintype "output"))
    )
    (net (code "161") (name "unconnected-(JTAG-Pad12)") (class "Default")
      (node (ref "JTAG") (pin "12") (pinfunction "12_12") (pintype "passive"))
    )
    (net (code "162") (name "unconnected-(JTAG-Pad14)") (class "Default")
      (node (ref "JTAG") (pin "14") (pinfunction "14_14") (pintype "passive"))
    )
    (net (code "163") (name "unconnected-(KME-RA3-Pad2)") (class "Default")
      (node (ref "KME") (pin "2") (pinfunction "RA3_2") (pintype "bidirectional"))
    )
    (net (code "164") (name "unconnected-(KME-RA4-Pad3)") (class "Default")
      (node (ref "KME") (pin "3") (pinfunction "RA4_3") (pintype "bidirectional"))
    )
    (net (code "165") (name "unconnected-(KME-RA7-Pad6)") (class "Default")
      (node (ref "KME") (pin "6") (pinfunction "RA7_6") (pintype "bidirectional"))
    )
    (net (code "166") (name "unconnected-(KME-RC0-Pad8)") (class "Default")
      (node (ref "KME") (pin "8") (pinfunction "RC0_8") (pintype "bidirectional"))
    )
    (net (code "167") (name "unconnected-(KME-RC1-Pad9)") (class "Default")
      (node (ref "KME") (pin "9") (pinfunction "RC1_9") (pintype "bidirectional"))
    )
    (net (code "168") (name "unconnected-(KMW-RB0-Pad18)") (class "Default")
      (node (ref "KMW") (pin "18") (pinfunction "RB0_18") (pintype "bidirectional"))
    )
    (net (code "169") (name "unconnected-(KMW-RB1-Pad19)") (class "Default")
      (node (ref "KMW") (pin "19") (pinfunction "RB1_19") (pintype "bidirectional"))
    )
    (net (code "170") (name "unconnected-(KMW-RB4-Pad22)") (class "Default")
      (node (ref "KMW") (pin "22") (pinfunction "RB4_22") (pintype "bidirectional"))
    )
    (net (code "171") (name "unconnected-(KMW-RC1-Pad9)") (class "Default")
      (node (ref "KMW") (pin "9") (pinfunction "RC1_9") (pintype "bidirectional"))
    )
    (net (code "172") (name "unconnected-(P1-Pad2)") (class "Default")
      (node (ref "P1") (pin "2") (pinfunction "2_2") (pintype "passive"))
    )
    (net (code "173") (name "unconnected-(P1-Pad3)") (class "Default")
      (node (ref "P1") (pin "3") (pinfunction "3_3") (pintype "passive"))
    )
    (net (code "174") (name "unconnected-(P2-Pad2)") (class "Default")
      (node (ref "P2") (pin "2") (pinfunction "2_2") (pintype "passive"))
    )
    (net (code "175") (name "unconnected-(P2-Pad3)") (class "Default")
      (node (ref "P2") (pin "3") (pinfunction "3_3") (pintype "passive"))
    )
    (net (code "176") (name "unconnected-(P3-Pad2)") (class "Default")
      (node (ref "P3") (pin "2") (pinfunction "2_2") (pintype "passive"))
    )
    (net (code "177") (name "unconnected-(P3-Pad3)") (class "Default")
      (node (ref "P3") (pin "3") (pinfunction "3_3") (pintype "passive"))
    )
    (net (code "178") (name "unconnected-(P4-Pad1)") (class "Default")
      (node (ref "P4") (pin "1") (pinfunction "1_1") (pintype "passive"))
    )
    (net (code "179") (name "unconnected-(P4-Pad4)") (class "Default")
      (node (ref "P4") (pin "4") (pinfunction "4_4") (pintype "passive"))
    )
    (net (code "180") (name "unconnected-(P5-Pad1)") (class "Default")
      (node (ref "P5") (pin "1") (pinfunction "1_1") (pintype "passive"))
    )
    (net (code "181") (name "unconnected-(P5-Pad4)") (class "Default")
      (node (ref "P5") (pin "4") (pinfunction "4_4") (pintype "passive"))
    )
    (net (code "182") (name "unconnected-(P6-Pad1)") (class "Default")
      (node (ref "P6") (pin "1") (pinfunction "1_1") (pintype "passive"))
    )
    (net (code "183") (name "unconnected-(P6-Pad4)") (class "Default")
      (node (ref "P6") (pin "4") (pinfunction "4_4") (pintype "passive"))
    )
    (net (code "184") (name "unconnected-(P7-Pad2)") (class "Default")
      (node (ref "P7") (pin "2") (pinfunction "2_2") (pintype "passive"))
    )
    (net (code "185") (name "unconnected-(P7-Pad3)") (class "Default")
      (node (ref "P7") (pin "3") (pinfunction "3_3") (pintype "passive"))
    )
    (net (code "186") (name "unconnected-(P8-Pad2)") (class "Default")
      (node (ref "P8") (pin "2") (pinfunction "2_2") (pintype "passive"))
    )
    (net (code "187") (name "unconnected-(P8-Pad3)") (class "Default")
      (node (ref "P8") (pin "3") (pinfunction "3_3") (pintype "passive"))
    )
    (net (code "188") (name "unconnected-(P9-Pad2)") (class "Default")
      (node (ref "P9") (pin "2") (pinfunction "2_2") (pintype "passive"))
    )
    (net (code "189") (name "unconnected-(P9-Pad3)") (class "Default")
      (node (ref "P9") (pin "3") (pinfunction "3_3") (pintype "passive"))
    )
    (net (code "190") (name "unconnected-(P10-Pad2)") (class "Default")
      (node (ref "P10") (pin "2") (pinfunction "2_2") (pintype "passive"))
    )
    (net (code "191") (name "unconnected-(P10-Pad3)") (class "Default")
      (node (ref "P10") (pin "3") (pinfunction "3_3") (pintype "passive"))
    )
    (net (code "192") (name "unconnected-(P11-Pad2)") (class "Default")
      (node (ref "P11") (pin "2") (pinfunction "2_2") (pintype "passive"))
    )
    (net (code "193") (name "unconnected-(P11-Pad3)") (class "Default")
      (node (ref "P11") (pin "3") (pinfunction "3_3") (pintype "passive"))
    )
    (net (code "194") (name "unconnected-(P12-Pad2)") (class "Default")
      (node (ref "P12") (pin "2") (pinfunction "2_2") (pintype "passive"))
    )
    (net (code "195") (name "unconnected-(P12-Pad3)") (class "Default")
      (node (ref "P12") (pin "3") (pinfunction "3_3") (pintype "passive"))
    )
    (net (code "196") (name "unconnected-(P13-Pad2)") (class "Default")
      (node (ref "P13") (pin "2") (pinfunction "2_2") (pintype "passive"))
    )
    (net (code "197") (name "unconnected-(P13-Pad3)") (class "Default")
      (node (ref "P13") (pin "3") (pinfunction "3_3") (pintype "passive"))
    )
    (net (code "198") (name "unconnected-(RESET-Pad2)") (class "Default")
      (node (ref "RESET") (pin "2") (pinfunction "2_2") (pintype "passive"))
    )
    (net (code "199") (name "unconnected-(RESET-Pad3)") (class "Default")
      (node (ref "RESET") (pin "3") (pinfunction "3_3") (pintype "passive"))
    )
    (net (code "200") (name "~{MCLR}") (class "Default")
      (node (ref "C54") (pin "1") (pinfunction "1_1") (pintype "passive"))
      (node (ref "ICSP") (pin "1") (pinfunction "1_1") (pintype "passive"))
      (node (ref "R48") (pin "2") (pinfunction "2_2") (pintype "passive"))
      (node (ref "R49") (pin "1") (pinfunction "1_1") (pintype "passive"))
      (node (ref "U1") (pin "15") (pinfunction "~{MCLR}_15") (pintype "bidirectional"))
    )
    (net (code "201") (name "~{SS6}") (class "Default")
      (node (ref "TFT") (pin "38") (pinfunction "/CS_38") (pintype "bidirectional"))
      (node (ref "U1") (pin "6") (pinfunction "PMA6_6") (pintype "bidirectional"))
      (node (ref "U1") (pin "68") (pinfunction "PMA15_68") (pintype "bidirectional"))
    )
  )
)
